# custom_keyboard.net
KiCad netlist of a schematic drawn in EAGLE
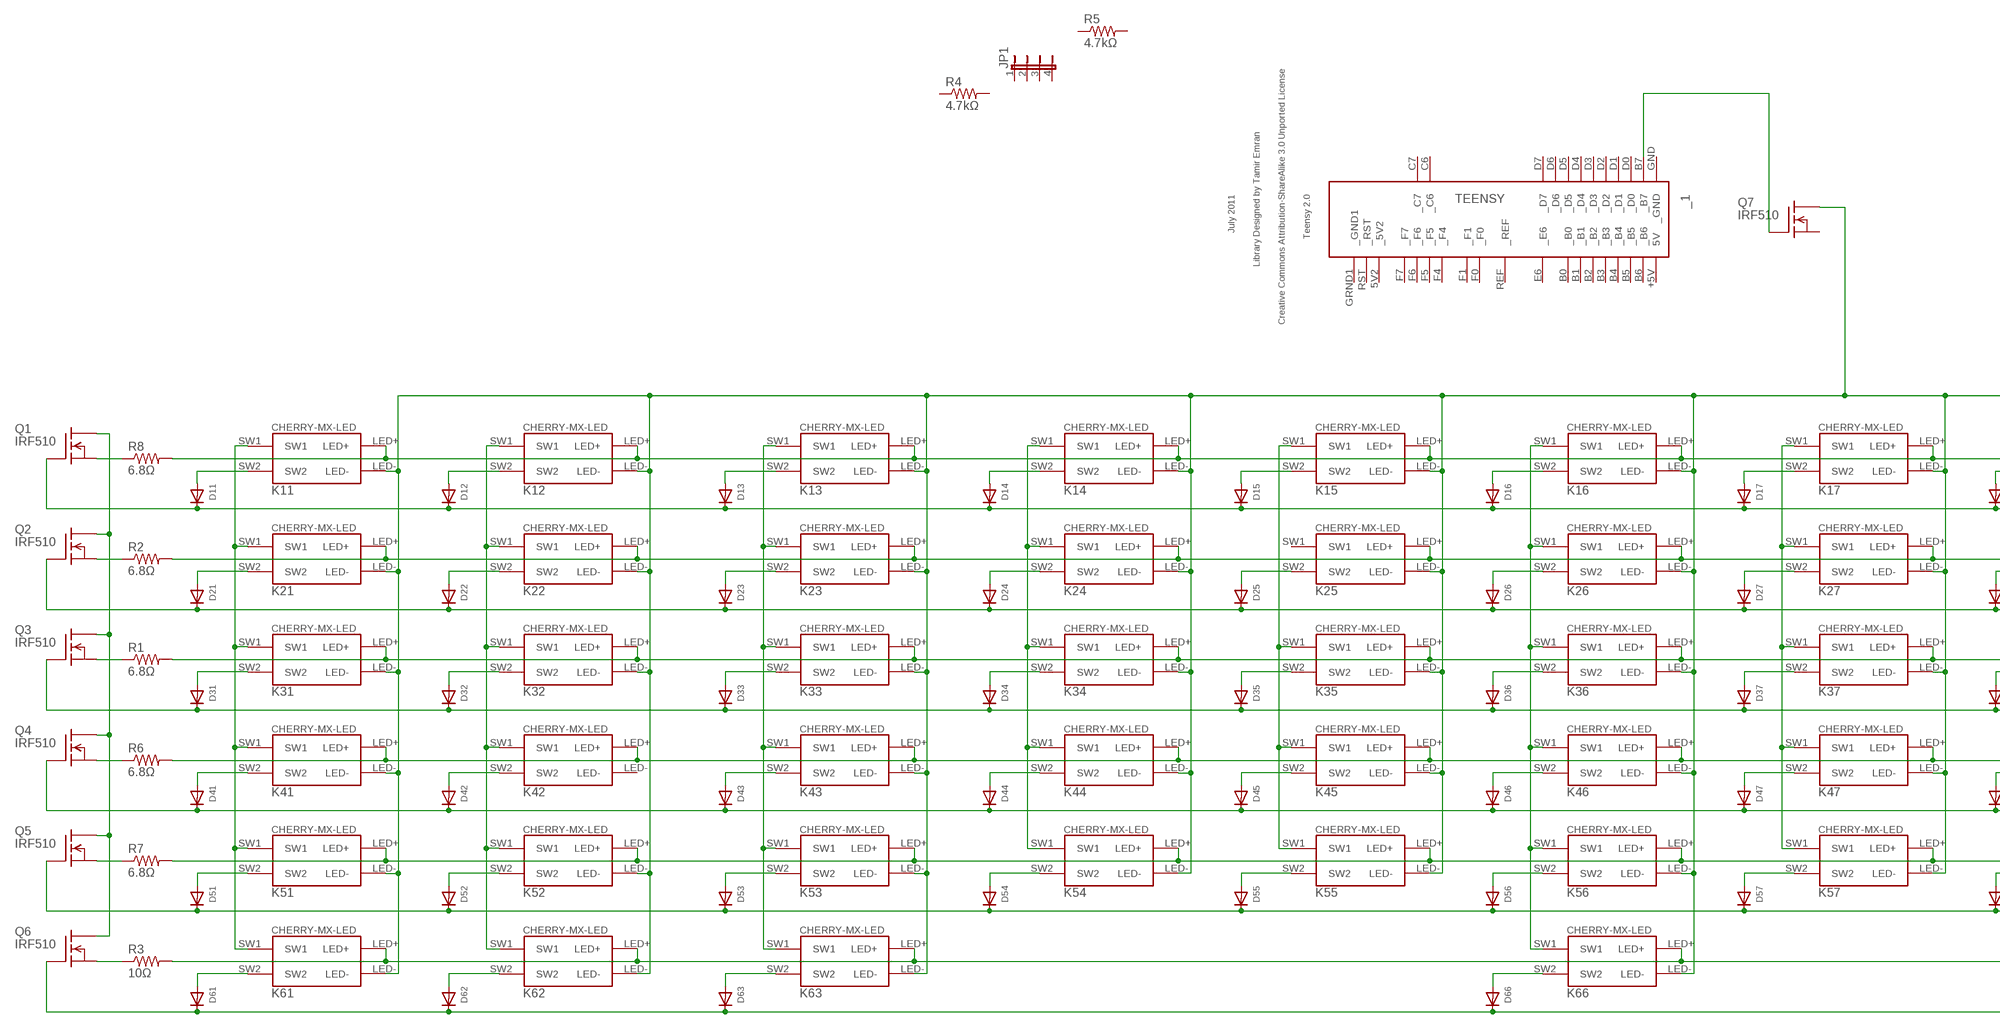
[diagram p0: schematic, sheet 1, part 1 of 2]
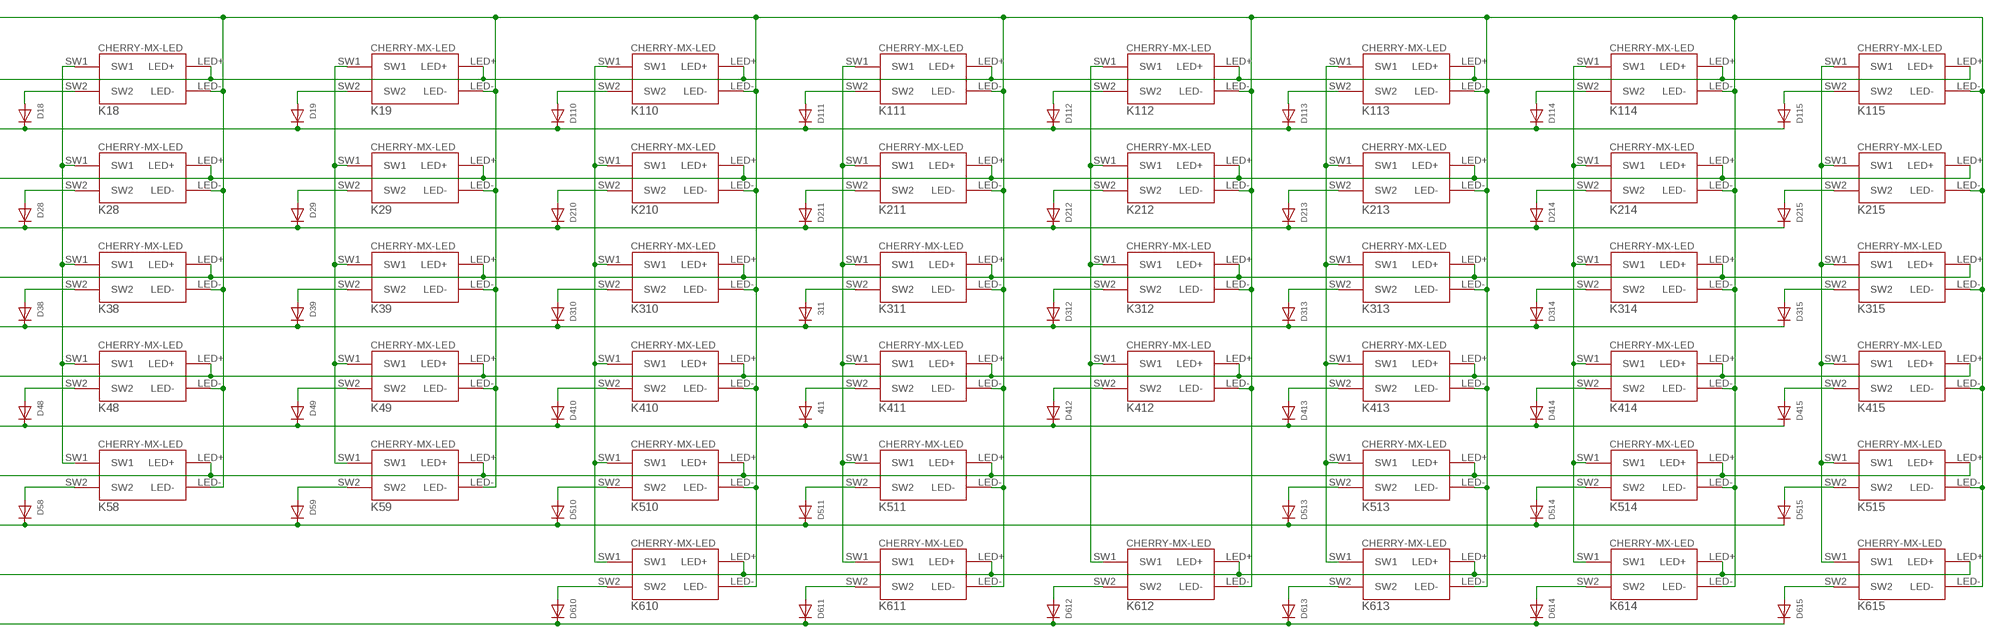
[diagram p1: schematic, sheet 1, part 2 of 2]

(export (version "E")
  (design (tool "Eeschema 10.0.6"))
  (components
    (comp (ref "311")
      (value "DIODEDO-1N4148")
      (footprint "eagle-import:DO-1N4148")
      (libsource (lib "eagle-import") (part "DIODEDO-1N4148"))
    )
    (comp (ref "411")
      (value "DIODEDO-1N4148")
      (footprint "eagle-import:DO-1N4148")
      (libsource (lib "eagle-import") (part "DIODEDO-1N4148"))
    )
    (comp (ref "D11")
      (value "DIODEDO-1N4148")
      (footprint "eagle-import:DO-1N4148")
      (libsource (lib "eagle-import") (part "DIODEDO-1N4148"))
    )
    (comp (ref "D12")
      (value "DIODEDO-1N4148")
      (footprint "eagle-import:DO-1N4148")
      (libsource (lib "eagle-import") (part "DIODEDO-1N4148"))
    )
    (comp (ref "D13")
      (value "DIODEDO-1N4148")
      (footprint "eagle-import:DO-1N4148")
      (libsource (lib "eagle-import") (part "DIODEDO-1N4148"))
    )
    (comp (ref "D14")
      (value "DIODEDO-1N4148")
      (footprint "eagle-import:DO-1N4148")
      (libsource (lib "eagle-import") (part "DIODEDO-1N4148"))
    )
    (comp (ref "D15")
      (value "DIODEDO-1N4148")
      (footprint "eagle-import:DO-1N4148")
      (libsource (lib "eagle-import") (part "DIODEDO-1N4148"))
    )
    (comp (ref "D16")
      (value "DIODEDO-1N4148")
      (footprint "eagle-import:DO-1N4148")
      (libsource (lib "eagle-import") (part "DIODEDO-1N4148"))
    )
    (comp (ref "D17")
      (value "DIODEDO-1N4148")
      (footprint "eagle-import:DO-1N4148")
      (libsource (lib "eagle-import") (part "DIODEDO-1N4148"))
    )
    (comp (ref "D18")
      (value "DIODEDO-1N4148")
      (footprint "eagle-import:DO-1N4148")
      (libsource (lib "eagle-import") (part "DIODEDO-1N4148"))
    )
    (comp (ref "D19")
      (value "DIODEDO-1N4148")
      (footprint "eagle-import:DO-1N4148")
      (libsource (lib "eagle-import") (part "DIODEDO-1N4148"))
    )
    (comp (ref "D21")
      (value "DIODEDO-1N4148")
      (footprint "eagle-import:DO-1N4148")
      (libsource (lib "eagle-import") (part "DIODEDO-1N4148"))
    )
    (comp (ref "D22")
      (value "DIODEDO-1N4148")
      (footprint "eagle-import:DO-1N4148")
      (libsource (lib "eagle-import") (part "DIODEDO-1N4148"))
    )
    (comp (ref "D23")
      (value "DIODEDO-1N4148")
      (footprint "eagle-import:DO-1N4148")
      (libsource (lib "eagle-import") (part "DIODEDO-1N4148"))
    )
    (comp (ref "D24")
      (value "DIODEDO-1N4148")
      (footprint "eagle-import:DO-1N4148")
      (libsource (lib "eagle-import") (part "DIODEDO-1N4148"))
    )
    (comp (ref "D25")
      (value "DIODEDO-1N4148")
      (footprint "eagle-import:DO-1N4148")
      (libsource (lib "eagle-import") (part "DIODEDO-1N4148"))
    )
    (comp (ref "D26")
      (value "DIODEDO-1N4148")
      (footprint "eagle-import:DO-1N4148")
      (libsource (lib "eagle-import") (part "DIODEDO-1N4148"))
    )
    (comp (ref "D27")
      (value "DIODEDO-1N4148")
      (footprint "eagle-import:DO-1N4148")
      (libsource (lib "eagle-import") (part "DIODEDO-1N4148"))
    )
    (comp (ref "D28")
      (value "DIODEDO-1N4148")
      (footprint "eagle-import:DO-1N4148")
      (libsource (lib "eagle-import") (part "DIODEDO-1N4148"))
    )
    (comp (ref "D29")
      (value "DIODEDO-1N4148")
      (footprint "eagle-import:DO-1N4148")
      (libsource (lib "eagle-import") (part "DIODEDO-1N4148"))
    )
    (comp (ref "D31")
      (value "DIODEDO-1N4148")
      (footprint "eagle-import:DO-1N4148")
      (libsource (lib "eagle-import") (part "DIODEDO-1N4148"))
    )
    (comp (ref "D32")
      (value "DIODEDO-1N4148")
      (footprint "eagle-import:DO-1N4148")
      (libsource (lib "eagle-import") (part "DIODEDO-1N4148"))
    )
    (comp (ref "D33")
      (value "DIODEDO-1N4148")
      (footprint "eagle-import:DO-1N4148")
      (libsource (lib "eagle-import") (part "DIODEDO-1N4148"))
    )
    (comp (ref "D34")
      (value "DIODEDO-1N4148")
      (footprint "eagle-import:DO-1N4148")
      (libsource (lib "eagle-import") (part "DIODEDO-1N4148"))
    )
    (comp (ref "D35")
      (value "DIODEDO-1N4148")
      (footprint "eagle-import:DO-1N4148")
      (libsource (lib "eagle-import") (part "DIODEDO-1N4148"))
    )
    (comp (ref "D36")
      (value "DIODEDO-1N4148")
      (footprint "eagle-import:DO-1N4148")
      (libsource (lib "eagle-import") (part "DIODEDO-1N4148"))
    )
    (comp (ref "D37")
      (value "DIODEDO-1N4148")
      (footprint "eagle-import:DO-1N4148")
      (libsource (lib "eagle-import") (part "DIODEDO-1N4148"))
    )
    (comp (ref "D38")
      (value "DIODEDO-1N4148")
      (footprint "eagle-import:DO-1N4148")
      (libsource (lib "eagle-import") (part "DIODEDO-1N4148"))
    )
    (comp (ref "D39")
      (value "DIODEDO-1N4148")
      (footprint "eagle-import:DO-1N4148")
      (libsource (lib "eagle-import") (part "DIODEDO-1N4148"))
    )
    (comp (ref "D41")
      (value "DIODEDO-1N4148")
      (footprint "eagle-import:DO-1N4148")
      (libsource (lib "eagle-import") (part "DIODEDO-1N4148"))
    )
    (comp (ref "D42")
      (value "DIODEDO-1N4148")
      (footprint "eagle-import:DO-1N4148")
      (libsource (lib "eagle-import") (part "DIODEDO-1N4148"))
    )
    (comp (ref "D43")
      (value "DIODEDO-1N4148")
      (footprint "eagle-import:DO-1N4148")
      (libsource (lib "eagle-import") (part "DIODEDO-1N4148"))
    )
    (comp (ref "D44")
      (value "DIODEDO-1N4148")
      (footprint "eagle-import:DO-1N4148")
      (libsource (lib "eagle-import") (part "DIODEDO-1N4148"))
    )
    (comp (ref "D45")
      (value "DIODEDO-1N4148")
      (footprint "eagle-import:DO-1N4148")
      (libsource (lib "eagle-import") (part "DIODEDO-1N4148"))
    )
    (comp (ref "D46")
      (value "DIODEDO-1N4148")
      (footprint "eagle-import:DO-1N4148")
      (libsource (lib "eagle-import") (part "DIODEDO-1N4148"))
    )
    (comp (ref "D47")
      (value "DIODEDO-1N4148")
      (footprint "eagle-import:DO-1N4148")
      (libsource (lib "eagle-import") (part "DIODEDO-1N4148"))
    )
    (comp (ref "D48")
      (value "DIODEDO-1N4148")
      (footprint "eagle-import:DO-1N4148")
      (libsource (lib "eagle-import") (part "DIODEDO-1N4148"))
    )
    (comp (ref "D49")
      (value "DIODEDO-1N4148")
      (footprint "eagle-import:DO-1N4148")
      (libsource (lib "eagle-import") (part "DIODEDO-1N4148"))
    )
    (comp (ref "D51")
      (value "DIODEDO-1N4148")
      (footprint "eagle-import:DO-1N4148")
      (libsource (lib "eagle-import") (part "DIODEDO-1N4148"))
    )
    (comp (ref "D52")
      (value "DIODEDO-1N4148")
      (footprint "eagle-import:DO-1N4148")
      (libsource (lib "eagle-import") (part "DIODEDO-1N4148"))
    )
    (comp (ref "D53")
      (value "DIODEDO-1N4148")
      (footprint "eagle-import:DO-1N4148")
      (libsource (lib "eagle-import") (part "DIODEDO-1N4148"))
    )
    (comp (ref "D54")
      (value "DIODEDO-1N4148")
      (footprint "eagle-import:DO-1N4148")
      (libsource (lib "eagle-import") (part "DIODEDO-1N4148"))
    )
    (comp (ref "D55")
      (value "DIODEDO-1N4148")
      (footprint "eagle-import:DO-1N4148")
      (libsource (lib "eagle-import") (part "DIODEDO-1N4148"))
    )
    (comp (ref "D56")
      (value "DIODEDO-1N4148")
      (footprint "eagle-import:DO-1N4148")
      (libsource (lib "eagle-import") (part "DIODEDO-1N4148"))
    )
    (comp (ref "D57")
      (value "DIODEDO-1N4148")
      (footprint "eagle-import:DO-1N4148")
      (libsource (lib "eagle-import") (part "DIODEDO-1N4148"))
    )
    (comp (ref "D58")
      (value "DIODEDO-1N4148")
      (footprint "eagle-import:DO-1N4148")
      (libsource (lib "eagle-import") (part "DIODEDO-1N4148"))
    )
    (comp (ref "D59")
      (value "DIODEDO-1N4148")
      (footprint "eagle-import:DO-1N4148")
      (libsource (lib "eagle-import") (part "DIODEDO-1N4148"))
    )
    (comp (ref "D61")
      (value "DIODEDO-1N4148")
      (footprint "eagle-import:DO-1N4148")
      (libsource (lib "eagle-import") (part "DIODEDO-1N4148"))
    )
    (comp (ref "D62")
      (value "DIODEDO-1N4148")
      (footprint "eagle-import:DO-1N4148")
      (libsource (lib "eagle-import") (part "DIODEDO-1N4148"))
    )
    (comp (ref "D63")
      (value "DIODEDO-1N4148")
      (footprint "eagle-import:DO-1N4148")
      (libsource (lib "eagle-import") (part "DIODEDO-1N4148"))
    )
    (comp (ref "D66")
      (value "DIODEDO-1N4148")
      (footprint "eagle-import:DO-1N4148")
      (libsource (lib "eagle-import") (part "DIODEDO-1N4148"))
    )
    (comp (ref "D110")
      (value "DIODEDO-1N4148")
      (footprint "eagle-import:DO-1N4148")
      (libsource (lib "eagle-import") (part "DIODEDO-1N4148"))
    )
    (comp (ref "D111")
      (value "DIODEDO-1N4148")
      (footprint "eagle-import:DO-1N4148")
      (libsource (lib "eagle-import") (part "DIODEDO-1N4148"))
    )
    (comp (ref "D112")
      (value "DIODEDO-1N4148")
      (footprint "eagle-import:DO-1N4148")
      (libsource (lib "eagle-import") (part "DIODEDO-1N4148"))
    )
    (comp (ref "D113")
      (value "DIODEDO-1N4148")
      (footprint "eagle-import:DO-1N4148")
      (libsource (lib "eagle-import") (part "DIODEDO-1N4148"))
    )
    (comp (ref "D114")
      (value "DIODEDO-1N4148")
      (footprint "eagle-import:DO-1N4148")
      (libsource (lib "eagle-import") (part "DIODEDO-1N4148"))
    )
    (comp (ref "D115")
      (value "DIODEDO-1N4148")
      (footprint "eagle-import:DO-1N4148")
      (libsource (lib "eagle-import") (part "DIODEDO-1N4148"))
    )
    (comp (ref "D210")
      (value "DIODEDO-1N4148")
      (footprint "eagle-import:DO-1N4148")
      (libsource (lib "eagle-import") (part "DIODEDO-1N4148"))
    )
    (comp (ref "D211")
      (value "DIODEDO-1N4148")
      (footprint "eagle-import:DO-1N4148")
      (libsource (lib "eagle-import") (part "DIODEDO-1N4148"))
    )
    (comp (ref "D212")
      (value "DIODEDO-1N4148")
      (footprint "eagle-import:DO-1N4148")
      (libsource (lib "eagle-import") (part "DIODEDO-1N4148"))
    )
    (comp (ref "D213")
      (value "DIODEDO-1N4148")
      (footprint "eagle-import:DO-1N4148")
      (libsource (lib "eagle-import") (part "DIODEDO-1N4148"))
    )
    (comp (ref "D214")
      (value "DIODEDO-1N4148")
      (footprint "eagle-import:DO-1N4148")
      (libsource (lib "eagle-import") (part "DIODEDO-1N4148"))
    )
    (comp (ref "D215")
      (value "DIODEDO-1N4148")
      (footprint "eagle-import:DO-1N4148")
      (libsource (lib "eagle-import") (part "DIODEDO-1N4148"))
    )
    (comp (ref "D310")
      (value "DIODEDO-1N4148")
      (footprint "eagle-import:DO-1N4148")
      (libsource (lib "eagle-import") (part "DIODEDO-1N4148"))
    )
    (comp (ref "D312")
      (value "DIODEDO-1N4148")
      (footprint "eagle-import:DO-1N4148")
      (libsource (lib "eagle-import") (part "DIODEDO-1N4148"))
    )
    (comp (ref "D313")
      (value "DIODEDO-1N4148")
      (footprint "eagle-import:DO-1N4148")
      (libsource (lib "eagle-import") (part "DIODEDO-1N4148"))
    )
    (comp (ref "D314")
      (value "DIODEDO-1N4148")
      (footprint "eagle-import:DO-1N4148")
      (libsource (lib "eagle-import") (part "DIODEDO-1N4148"))
    )
    (comp (ref "D315")
      (value "DIODEDO-1N4148")
      (footprint "eagle-import:DO-1N4148")
      (libsource (lib "eagle-import") (part "DIODEDO-1N4148"))
    )
    (comp (ref "D410")
      (value "DIODEDO-1N4148")
      (footprint "eagle-import:DO-1N4148")
      (libsource (lib "eagle-import") (part "DIODEDO-1N4148"))
    )
    (comp (ref "D412")
      (value "DIODEDO-1N4148")
      (footprint "eagle-import:DO-1N4148")
      (libsource (lib "eagle-import") (part "DIODEDO-1N4148"))
    )
    (comp (ref "D413")
      (value "DIODEDO-1N4148")
      (footprint "eagle-import:DO-1N4148")
      (libsource (lib "eagle-import") (part "DIODEDO-1N4148"))
    )
    (comp (ref "D414")
      (value "DIODEDO-1N4148")
      (footprint "eagle-import:DO-1N4148")
      (libsource (lib "eagle-import") (part "DIODEDO-1N4148"))
    )
    (comp (ref "D415")
      (value "DIODEDO-1N4148")
      (footprint "eagle-import:DO-1N4148")
      (libsource (lib "eagle-import") (part "DIODEDO-1N4148"))
    )
    (comp (ref "D510")
      (value "DIODEDO-1N4148")
      (footprint "eagle-import:DO-1N4148")
      (libsource (lib "eagle-import") (part "DIODEDO-1N4148"))
    )
    (comp (ref "D511")
      (value "DIODEDO-1N4148")
      (footprint "eagle-import:DO-1N4148")
      (libsource (lib "eagle-import") (part "DIODEDO-1N4148"))
    )
    (comp (ref "D513")
      (value "DIODEDO-1N4148")
      (footprint "eagle-import:DO-1N4148")
      (libsource (lib "eagle-import") (part "DIODEDO-1N4148"))
    )
    (comp (ref "D514")
      (value "DIODEDO-1N4148")
      (footprint "eagle-import:DO-1N4148")
      (libsource (lib "eagle-import") (part "DIODEDO-1N4148"))
    )
    (comp (ref "D515")
      (value "DIODEDO-1N4148")
      (footprint "eagle-import:DO-1N4148")
      (libsource (lib "eagle-import") (part "DIODEDO-1N4148"))
    )
    (comp (ref "D610")
      (value "DIODEDO-1N4148")
      (footprint "eagle-import:DO-1N4148")
      (libsource (lib "eagle-import") (part "DIODEDO-1N4148"))
    )
    (comp (ref "D611")
      (value "DIODEDO-1N4148")
      (footprint "eagle-import:DO-1N4148")
      (libsource (lib "eagle-import") (part "DIODEDO-1N4148"))
    )
    (comp (ref "D612")
      (value "DIODEDO-1N4148")
      (footprint "eagle-import:DO-1N4148")
      (libsource (lib "eagle-import") (part "DIODEDO-1N4148"))
    )
    (comp (ref "D613")
      (value "DIODEDO-1N4148")
      (footprint "eagle-import:DO-1N4148")
      (libsource (lib "eagle-import") (part "DIODEDO-1N4148"))
    )
    (comp (ref "D614")
      (value "DIODEDO-1N4148")
      (footprint "eagle-import:DO-1N4148")
      (libsource (lib "eagle-import") (part "DIODEDO-1N4148"))
    )
    (comp (ref "D615")
      (value "DIODEDO-1N4148")
      (footprint "eagle-import:DO-1N4148")
      (libsource (lib "eagle-import") (part "DIODEDO-1N4148"))
    )
    (comp (ref "JP1")
      (value "JP4E")
      (footprint "eagle-import:JP4")
      (libsource (lib "eagle-import") (part "JP4E"))
    )
    (comp (ref "K11")
      (value "CHERRY-MX-LED")
      (footprint "eagle-import:CHERRY-MX-LED")
      (libsource (lib "eagle-import") (part "CHERRY-MX-LED"))
    )
    (comp (ref "K12")
      (value "CHERRY-MX-LED")
      (footprint "eagle-import:CHERRY-MX-LED")
      (libsource (lib "eagle-import") (part "CHERRY-MX-LED"))
    )
    (comp (ref "K13")
      (value "CHERRY-MX-LED")
      (footprint "eagle-import:CHERRY-MX-LED")
      (libsource (lib "eagle-import") (part "CHERRY-MX-LED"))
    )
    (comp (ref "K14")
      (value "CHERRY-MX-LED")
      (footprint "eagle-import:CHERRY-MX-LED")
      (libsource (lib "eagle-import") (part "CHERRY-MX-LED"))
    )
    (comp (ref "K15")
      (value "CHERRY-MX-LED")
      (footprint "eagle-import:CHERRY-MX-LED")
      (libsource (lib "eagle-import") (part "CHERRY-MX-LED"))
    )
    (comp (ref "K16")
      (value "CHERRY-MX-LED")
      (footprint "eagle-import:CHERRY-MX-LED")
      (libsource (lib "eagle-import") (part "CHERRY-MX-LED"))
    )
    (comp (ref "K17")
      (value "CHERRY-MX-LED")
      (footprint "eagle-import:CHERRY-MX-LED")
      (libsource (lib "eagle-import") (part "CHERRY-MX-LED"))
    )
    (comp (ref "K18")
      (value "CHERRY-MX-LED")
      (footprint "eagle-import:CHERRY-MX-LED")
      (libsource (lib "eagle-import") (part "CHERRY-MX-LED"))
    )
    (comp (ref "K19")
      (value "CHERRY-MX-LED")
      (footprint "eagle-import:CHERRY-MX-LED")
      (libsource (lib "eagle-import") (part "CHERRY-MX-LED"))
    )
    (comp (ref "K21")
      (value "CHERRY-MX-LED")
      (footprint "eagle-import:CHERRY-MX-LED")
      (libsource (lib "eagle-import") (part "CHERRY-MX-LED"))
    )
    (comp (ref "K22")
      (value "CHERRY-MX-LED")
      (footprint "eagle-import:CHERRY-MX-LED")
      (libsource (lib "eagle-import") (part "CHERRY-MX-LED"))
    )
    (comp (ref "K23")
      (value "CHERRY-MX-LED")
      (footprint "eagle-import:CHERRY-MX-LED")
      (libsource (lib "eagle-import") (part "CHERRY-MX-LED"))
    )
    (comp (ref "K24")
      (value "CHERRY-MX-LED")
      (footprint "eagle-import:CHERRY-MX-LED")
      (libsource (lib "eagle-import") (part "CHERRY-MX-LED"))
    )
    (comp (ref "K25")
      (value "CHERRY-MX-LED")
      (footprint "eagle-import:CHERRY-MX-LED")
      (libsource (lib "eagle-import") (part "CHERRY-MX-LED"))
    )
    (comp (ref "K26")
      (value "CHERRY-MX-LED")
      (footprint "eagle-import:CHERRY-MX-LED")
      (libsource (lib "eagle-import") (part "CHERRY-MX-LED"))
    )
    (comp (ref "K27")
      (value "CHERRY-MX-LED")
      (footprint "eagle-import:CHERRY-MX-LED")
      (libsource (lib "eagle-import") (part "CHERRY-MX-LED"))
    )
    (comp (ref "K28")
      (value "CHERRY-MX-LED")
      (footprint "eagle-import:CHERRY-MX-LED")
      (libsource (lib "eagle-import") (part "CHERRY-MX-LED"))
    )
    (comp (ref "K29")
      (value "CHERRY-MX-LED")
      (footprint "eagle-import:CHERRY-MX-LED")
      (libsource (lib "eagle-import") (part "CHERRY-MX-LED"))
    )
    (comp (ref "K31")
      (value "CHERRY-MX-LED")
      (footprint "eagle-import:CHERRY-MX-LED")
      (libsource (lib "eagle-import") (part "CHERRY-MX-LED"))
    )
    (comp (ref "K32")
      (value "CHERRY-MX-LED")
      (footprint "eagle-import:CHERRY-MX-LED")
      (libsource (lib "eagle-import") (part "CHERRY-MX-LED"))
    )
    (comp (ref "K33")
      (value "CHERRY-MX-LED")
      (footprint "eagle-import:CHERRY-MX-LED")
      (libsource (lib "eagle-import") (part "CHERRY-MX-LED"))
    )
    (comp (ref "K34")
      (value "CHERRY-MX-LED")
      (footprint "eagle-import:CHERRY-MX-LED")
      (libsource (lib "eagle-import") (part "CHERRY-MX-LED"))
    )
    (comp (ref "K35")
      (value "CHERRY-MX-LED")
      (footprint "eagle-import:CHERRY-MX-LED")
      (libsource (lib "eagle-import") (part "CHERRY-MX-LED"))
    )
    (comp (ref "K36")
      (value "CHERRY-MX-LED")
      (footprint "eagle-import:CHERRY-MX-LED")
      (libsource (lib "eagle-import") (part "CHERRY-MX-LED"))
    )
    (comp (ref "K37")
      (value "CHERRY-MX-LED")
      (footprint "eagle-import:CHERRY-MX-LED")
      (libsource (lib "eagle-import") (part "CHERRY-MX-LED"))
    )
    (comp (ref "K38")
      (value "CHERRY-MX-LED")
      (footprint "eagle-import:CHERRY-MX-LED")
      (libsource (lib "eagle-import") (part "CHERRY-MX-LED"))
    )
    (comp (ref "K39")
      (value "CHERRY-MX-LED")
      (footprint "eagle-import:CHERRY-MX-LED")
      (libsource (lib "eagle-import") (part "CHERRY-MX-LED"))
    )
    (comp (ref "K41")
      (value "CHERRY-MX-LED")
      (footprint "eagle-import:CHERRY-MX-LED")
      (libsource (lib "eagle-import") (part "CHERRY-MX-LED"))
    )
    (comp (ref "K42")
      (value "CHERRY-MX-LED")
      (footprint "eagle-import:CHERRY-MX-LED")
      (libsource (lib "eagle-import") (part "CHERRY-MX-LED"))
    )
    (comp (ref "K43")
      (value "CHERRY-MX-LED")
      (footprint "eagle-import:CHERRY-MX-LED")
      (libsource (lib "eagle-import") (part "CHERRY-MX-LED"))
    )
    (comp (ref "K44")
      (value "CHERRY-MX-LED")
      (footprint "eagle-import:CHERRY-MX-LED")
      (libsource (lib "eagle-import") (part "CHERRY-MX-LED"))
    )
    (comp (ref "K45")
      (value "CHERRY-MX-LED")
      (footprint "eagle-import:CHERRY-MX-LED")
      (libsource (lib "eagle-import") (part "CHERRY-MX-LED"))
    )
    (comp (ref "K46")
      (value "CHERRY-MX-LED")
      (footprint "eagle-import:CHERRY-MX-LED")
      (libsource (lib "eagle-import") (part "CHERRY-MX-LED"))
    )
    (comp (ref "K47")
      (value "CHERRY-MX-LED")
      (footprint "eagle-import:CHERRY-MX-LED")
      (libsource (lib "eagle-import") (part "CHERRY-MX-LED"))
    )
    (comp (ref "K48")
      (value "CHERRY-MX-LED")
      (footprint "eagle-import:CHERRY-MX-LED")
      (libsource (lib "eagle-import") (part "CHERRY-MX-LED"))
    )
    (comp (ref "K49")
      (value "CHERRY-MX-LED")
      (footprint "eagle-import:CHERRY-MX-LED")
      (libsource (lib "eagle-import") (part "CHERRY-MX-LED"))
    )
    (comp (ref "K51")
      (value "CHERRY-MX-LED")
      (footprint "eagle-import:CHERRY-MX-LED")
      (libsource (lib "eagle-import") (part "CHERRY-MX-LED"))
    )
    (comp (ref "K52")
      (value "CHERRY-MX-LED")
      (footprint "eagle-import:CHERRY-MX-LED")
      (libsource (lib "eagle-import") (part "CHERRY-MX-LED"))
    )
    (comp (ref "K53")
      (value "CHERRY-MX-LED")
      (footprint "eagle-import:CHERRY-MX-LED")
      (libsource (lib "eagle-import") (part "CHERRY-MX-LED"))
    )
    (comp (ref "K54")
      (value "CHERRY-MX-LED")
      (footprint "eagle-import:CHERRY-MX-LED")
      (libsource (lib "eagle-import") (part "CHERRY-MX-LED"))
    )
    (comp (ref "K55")
      (value "CHERRY-MX-LED")
      (footprint "eagle-import:CHERRY-MX-LED")
      (libsource (lib "eagle-import") (part "CHERRY-MX-LED"))
    )
    (comp (ref "K56")
      (value "CHERRY-MX-LED")
      (footprint "eagle-import:CHERRY-MX-LED")
      (libsource (lib "eagle-import") (part "CHERRY-MX-LED"))
    )
    (comp (ref "K57")
      (value "CHERRY-MX-LED")
      (footprint "eagle-import:CHERRY-MX-LED")
      (libsource (lib "eagle-import") (part "CHERRY-MX-LED"))
    )
    (comp (ref "K58")
      (value "CHERRY-MX-LED")
      (footprint "eagle-import:CHERRY-MX-LED")
      (libsource (lib "eagle-import") (part "CHERRY-MX-LED"))
    )
    (comp (ref "K59")
      (value "CHERRY-MX-LED")
      (footprint "eagle-import:CHERRY-MX-LED")
      (libsource (lib "eagle-import") (part "CHERRY-MX-LED"))
    )
    (comp (ref "K61")
      (value "CHERRY-MX-LED")
      (footprint "eagle-import:CHERRY-MX-LED")
      (libsource (lib "eagle-import") (part "CHERRY-MX-LED"))
    )
    (comp (ref "K62")
      (value "CHERRY-MX-LED")
      (footprint "eagle-import:CHERRY-MX-LED")
      (libsource (lib "eagle-import") (part "CHERRY-MX-LED"))
    )
    (comp (ref "K63")
      (value "CHERRY-MX-LED")
      (footprint "eagle-import:CHERRY-MX-LED")
      (libsource (lib "eagle-import") (part "CHERRY-MX-LED"))
    )
    (comp (ref "K66")
      (value "CHERRY-MX-LED")
      (footprint "eagle-import:CHERRY-MX-LED")
      (libsource (lib "eagle-import") (part "CHERRY-MX-LED"))
    )
    (comp (ref "K110")
      (value "CHERRY-MX-LED")
      (footprint "eagle-import:CHERRY-MX-LED")
      (libsource (lib "eagle-import") (part "CHERRY-MX-LED"))
    )
    (comp (ref "K111")
      (value "CHERRY-MX-LED")
      (footprint "eagle-import:CHERRY-MX-LED")
      (libsource (lib "eagle-import") (part "CHERRY-MX-LED"))
    )
    (comp (ref "K112")
      (value "CHERRY-MX-LED")
      (footprint "eagle-import:CHERRY-MX-LED")
      (libsource (lib "eagle-import") (part "CHERRY-MX-LED"))
    )
    (comp (ref "K113")
      (value "CHERRY-MX-LED")
      (footprint "eagle-import:CHERRY-MX-LED")
      (libsource (lib "eagle-import") (part "CHERRY-MX-LED"))
    )
    (comp (ref "K114")
      (value "CHERRY-MX-LED")
      (footprint "eagle-import:CHERRY-MX-LED")
      (libsource (lib "eagle-import") (part "CHERRY-MX-LED"))
    )
    (comp (ref "K115")
      (value "CHERRY-MX-LED")
      (footprint "eagle-import:CHERRY-MX-LED")
      (libsource (lib "eagle-import") (part "CHERRY-MX-LED"))
    )
    (comp (ref "K210")
      (value "CHERRY-MX-LED")
      (footprint "eagle-import:CHERRY-MX-LED")
      (libsource (lib "eagle-import") (part "CHERRY-MX-LED"))
    )
    (comp (ref "K211")
      (value "CHERRY-MX-LED")
      (footprint "eagle-import:CHERRY-MX-LED")
      (libsource (lib "eagle-import") (part "CHERRY-MX-LED"))
    )
    (comp (ref "K212")
      (value "CHERRY-MX-LED")
      (footprint "eagle-import:CHERRY-MX-LED")
      (libsource (lib "eagle-import") (part "CHERRY-MX-LED"))
    )
    (comp (ref "K213")
      (value "CHERRY-MX-LED")
      (footprint "eagle-import:CHERRY-MX-LED")
      (libsource (lib "eagle-import") (part "CHERRY-MX-LED"))
    )
    (comp (ref "K214")
      (value "CHERRY-MX-LED")
      (footprint "eagle-import:CHERRY-MX-LED")
      (libsource (lib "eagle-import") (part "CHERRY-MX-LED"))
    )
    (comp (ref "K215")
      (value "CHERRY-MX-LED")
      (footprint "eagle-import:CHERRY-MX-LED")
      (libsource (lib "eagle-import") (part "CHERRY-MX-LED"))
    )
    (comp (ref "K310")
      (value "CHERRY-MX-LED")
      (footprint "eagle-import:CHERRY-MX-LED")
      (libsource (lib "eagle-import") (part "CHERRY-MX-LED"))
    )
    (comp (ref "K311")
      (value "CHERRY-MX-LED")
      (footprint "eagle-import:CHERRY-MX-LED")
      (libsource (lib "eagle-import") (part "CHERRY-MX-LED"))
    )
    (comp (ref "K312")
      (value "CHERRY-MX-LED")
      (footprint "eagle-import:CHERRY-MX-LED")
      (libsource (lib "eagle-import") (part "CHERRY-MX-LED"))
    )
    (comp (ref "K313")
      (value "CHERRY-MX-LED")
      (footprint "eagle-import:CHERRY-MX-LED")
      (libsource (lib "eagle-import") (part "CHERRY-MX-LED"))
    )
    (comp (ref "K314")
      (value "CHERRY-MX-LED")
      (footprint "eagle-import:CHERRY-MX-LED")
      (libsource (lib "eagle-import") (part "CHERRY-MX-LED"))
    )
    (comp (ref "K315")
      (value "CHERRY-MX-LED")
      (footprint "eagle-import:CHERRY-MX-LED")
      (libsource (lib "eagle-import") (part "CHERRY-MX-LED"))
    )
    (comp (ref "K410")
      (value "CHERRY-MX-LED")
      (footprint "eagle-import:CHERRY-MX-LED")
      (libsource (lib "eagle-import") (part "CHERRY-MX-LED"))
    )
    (comp (ref "K411")
      (value "CHERRY-MX-LED")
      (footprint "eagle-import:CHERRY-MX-LED")
      (libsource (lib "eagle-import") (part "CHERRY-MX-LED"))
    )
    (comp (ref "K412")
      (value "CHERRY-MX-LED")
      (footprint "eagle-import:CHERRY-MX-LED")
      (libsource (lib "eagle-import") (part "CHERRY-MX-LED"))
    )
    (comp (ref "K413")
      (value "CHERRY-MX-LED")
      (footprint "eagle-import:CHERRY-MX-LED")
      (libsource (lib "eagle-import") (part "CHERRY-MX-LED"))
    )
    (comp (ref "K414")
      (value "CHERRY-MX-LED")
      (footprint "eagle-import:CHERRY-MX-LED")
      (libsource (lib "eagle-import") (part "CHERRY-MX-LED"))
    )
    (comp (ref "K415")
      (value "CHERRY-MX-LED")
      (footprint "eagle-import:CHERRY-MX-LED")
      (libsource (lib "eagle-import") (part "CHERRY-MX-LED"))
    )
    (comp (ref "K510")
      (value "CHERRY-MX-LED")
      (footprint "eagle-import:CHERRY-MX-LED")
      (libsource (lib "eagle-import") (part "CHERRY-MX-LED"))
    )
    (comp (ref "K511")
      (value "CHERRY-MX-LED")
      (footprint "eagle-import:CHERRY-MX-LED")
      (libsource (lib "eagle-import") (part "CHERRY-MX-LED"))
    )
    (comp (ref "K513")
      (value "CHERRY-MX-LED")
      (footprint "eagle-import:CHERRY-MX-LED")
      (libsource (lib "eagle-import") (part "CHERRY-MX-LED"))
    )
    (comp (ref "K514")
      (value "CHERRY-MX-LED")
      (footprint "eagle-import:CHERRY-MX-LED")
      (libsource (lib "eagle-import") (part "CHERRY-MX-LED"))
    )
    (comp (ref "K515")
      (value "CHERRY-MX-LED")
      (footprint "eagle-import:CHERRY-MX-LED")
      (libsource (lib "eagle-import") (part "CHERRY-MX-LED"))
    )
    (comp (ref "K610")
      (value "CHERRY-MX-LED")
      (footprint "eagle-import:CHERRY-MX-LED")
      (libsource (lib "eagle-import") (part "CHERRY-MX-LED"))
    )
    (comp (ref "K611")
      (value "CHERRY-MX-LED")
      (footprint "eagle-import:CHERRY-MX-LED")
      (libsource (lib "eagle-import") (part "CHERRY-MX-LED"))
    )
    (comp (ref "K612")
      (value "CHERRY-MX-LED")
      (footprint "eagle-import:CHERRY-MX-LED")
      (libsource (lib "eagle-import") (part "CHERRY-MX-LED"))
    )
    (comp (ref "K613")
      (value "CHERRY-MX-LED")
      (footprint "eagle-import:CHERRY-MX-LED")
      (libsource (lib "eagle-import") (part "CHERRY-MX-LED"))
    )
    (comp (ref "K614")
      (value "CHERRY-MX-LED")
      (footprint "eagle-import:CHERRY-MX-LED")
      (libsource (lib "eagle-import") (part "CHERRY-MX-LED"))
    )
    (comp (ref "K615")
      (value "CHERRY-MX-LED")
      (footprint "eagle-import:CHERRY-MX-LED")
      (libsource (lib "eagle-import") (part "CHERRY-MX-LED"))
    )
    (comp (ref "Q1")
      (value "IRF510")
      (footprint "eagle-import:TO220")
      (libsource (lib "eagle-import") (part "IRF510"))
    )
    (comp (ref "Q2")
      (value "IRF510")
      (footprint "eagle-import:TO220")
      (libsource (lib "eagle-import") (part "IRF510"))
    )
    (comp (ref "Q3")
      (value "IRF510")
      (footprint "eagle-import:TO220")
      (libsource (lib "eagle-import") (part "IRF510"))
    )
    (comp (ref "Q4")
      (value "IRF510")
      (footprint "eagle-import:TO220")
      (libsource (lib "eagle-import") (part "IRF510"))
    )
    (comp (ref "Q5")
      (value "IRF510")
      (footprint "eagle-import:TO220")
      (libsource (lib "eagle-import") (part "IRF510"))
    )
    (comp (ref "Q6")
      (value "IRF510")
      (footprint "eagle-import:TO220")
      (libsource (lib "eagle-import") (part "IRF510"))
    )
    (comp (ref "Q7")
      (value "IRF510")
      (footprint "eagle-import:TO220")
      (libsource (lib "eagle-import") (part "IRF510"))
    )
    (comp (ref "R1")
      (value "6.8Ω")
      (footprint "eagle-import:0411_12")
      (libsource (lib "eagle-import") (part "R-US_0411/12"))
    )
    (comp (ref "R2")
      (value "6.8Ω")
      (footprint "eagle-import:0411_12")
      (libsource (lib "eagle-import") (part "R-US_0411/12"))
    )
    (comp (ref "R3")
      (value "10Ω")
      (footprint "eagle-import:0411_12")
      (libsource (lib "eagle-import") (part "R-US_0411/12"))
    )
    (comp (ref "R4")
      (value "4.7kΩ")
      (footprint "eagle-import:0204_7")
      (libsource (lib "eagle-import") (part "R-US_0204/7"))
    )
    (comp (ref "R5")
      (value "4.7kΩ")
      (footprint "eagle-import:0204_7")
      (libsource (lib "eagle-import") (part "R-US_0204/7"))
    )
    (comp (ref "R6")
      (value "6.8Ω")
      (footprint "eagle-import:0411_12")
      (libsource (lib "eagle-import") (part "R-US_0411/12"))
    )
    (comp (ref "R7")
      (value "6.8Ω")
      (footprint "eagle-import:0411_12")
      (libsource (lib "eagle-import") (part "R-US_0411/12"))
    )
    (comp (ref "R8")
      (value "6.8Ω")
      (footprint "eagle-import:0411_12")
      (libsource (lib "eagle-import") (part "R-US_0411/12"))
    )
    (comp (ref "_1")
      (value "TEENSY")
      (footprint "eagle-import:TEENSY")
      (libsource (lib "eagle-import") (part "TEENSY"))
    )
  )
  (nets
    (net (code "1") (name "Net-(311-PadA)") (class "Default")
      (node (ref "311") (pin "A") (pinfunction "A_A") (pintype "passive"))
      (node (ref "K311") (pin "SW2") (pinfunction "SW2_SW2") (pintype "bidirectional"))
    )
    (net (code "2") (name "Net-(411-PadA)") (class "Default")
      (node (ref "411") (pin "A") (pinfunction "A_A") (pintype "passive"))
      (node (ref "K411") (pin "SW2") (pinfunction "SW2_SW2") (pintype "bidirectional"))
    )
    (net (code "3") (name "Net-(D11-PadA)") (class "Default")
      (node (ref "D11") (pin "A") (pinfunction "A_A") (pintype "passive"))
      (node (ref "K11") (pin "SW2") (pinfunction "SW2_SW2") (pintype "bidirectional"))
    )
    (net (code "4") (name "Net-(D12-PadA)") (class "Default")
      (node (ref "D12") (pin "A") (pinfunction "A_A") (pintype "passive"))
      (node (ref "K12") (pin "SW2") (pinfunction "SW2_SW2") (pintype "bidirectional"))
    )
    (net (code "5") (name "Net-(D13-PadA)") (class "Default")
      (node (ref "D13") (pin "A") (pinfunction "A_A") (pintype "passive"))
      (node (ref "K13") (pin "SW2") (pinfunction "SW2_SW2") (pintype "bidirectional"))
    )
    (net (code "6") (name "Net-(D14-PadA)") (class "Default")
      (node (ref "D14") (pin "A") (pinfunction "A_A") (pintype "passive"))
      (node (ref "K14") (pin "SW2") (pinfunction "SW2_SW2") (pintype "bidirectional"))
    )
    (net (code "7") (name "Net-(D15-PadA)") (class "Default")
      (node (ref "D15") (pin "A") (pinfunction "A_A") (pintype "passive"))
      (node (ref "K15") (pin "SW2") (pinfunction "SW2_SW2") (pintype "bidirectional"))
    )
    (net (code "8") (name "Net-(D16-PadA)") (class "Default")
      (node (ref "D16") (pin "A") (pinfunction "A_A") (pintype "passive"))
      (node (ref "K16") (pin "SW2") (pinfunction "SW2_SW2") (pintype "bidirectional"))
    )
    (net (code "9") (name "Net-(D17-PadA)") (class "Default")
      (node (ref "D17") (pin "A") (pinfunction "A_A") (pintype "passive"))
      (node (ref "K17") (pin "SW2") (pinfunction "SW2_SW2") (pintype "bidirectional"))
    )
    (net (code "10") (name "Net-(D18-PadA)") (class "Default")
      (node (ref "D18") (pin "A") (pinfunction "A_A") (pintype "passive"))
      (node (ref "K18") (pin "SW2") (pinfunction "SW2_SW2") (pintype "bidirectional"))
    )
    (net (code "11") (name "Net-(D19-PadA)") (class "Default")
      (node (ref "D19") (pin "A") (pinfunction "A_A") (pintype "passive"))
      (node (ref "K19") (pin "SW2") (pinfunction "SW2_SW2") (pintype "bidirectional"))
    )
    (net (code "12") (name "Net-(D21-PadA)") (class "Default")
      (node (ref "D21") (pin "A") (pinfunction "A_A") (pintype "passive"))
      (node (ref "K21") (pin "SW2") (pinfunction "SW2_SW2") (pintype "bidirectional"))
    )
    (net (code "13") (name "Net-(D22-PadA)") (class "Default")
      (node (ref "D22") (pin "A") (pinfunction "A_A") (pintype "passive"))
      (node (ref "K22") (pin "SW2") (pinfunction "SW2_SW2") (pintype "bidirectional"))
    )
    (net (code "14") (name "Net-(D23-PadA)") (class "Default")
      (node (ref "D23") (pin "A") (pinfunction "A_A") (pintype "passive"))
      (node (ref "K23") (pin "SW2") (pinfunction "SW2_SW2") (pintype "bidirectional"))
    )
    (net (code "15") (name "Net-(D24-PadA)") (class "Default")
      (node (ref "D24") (pin "A") (pinfunction "A_A") (pintype "passive"))
      (node (ref "K24") (pin "SW2") (pinfunction "SW2_SW2") (pintype "bidirectional"))
    )
    (net (code "16") (name "Net-(D25-PadA)") (class "Default")
      (node (ref "D25") (pin "A") (pinfunction "A_A") (pintype "passive"))
      (node (ref "K25") (pin "SW2") (pinfunction "SW2_SW2") (pintype "bidirectional"))
    )
    (net (code "17") (name "Net-(D26-PadA)") (class "Default")
      (node (ref "D26") (pin "A") (pinfunction "A_A") (pintype "passive"))
      (node (ref "K26") (pin "SW2") (pinfunction "SW2_SW2") (pintype "bidirectional"))
    )
    (net (code "18") (name "Net-(D27-PadA)") (class "Default")
      (node (ref "D27") (pin "A") (pinfunction "A_A") (pintype "passive"))
      (node (ref "K27") (pin "SW2") (pinfunction "SW2_SW2") (pintype "bidirectional"))
    )
    (net (code "19") (name "Net-(D28-PadA)") (class "Default")
      (node (ref "D28") (pin "A") (pinfunction "A_A") (pintype "passive"))
      (node (ref "K28") (pin "SW2") (pinfunction "SW2_SW2") (pintype "bidirectional"))
    )
    (net (code "20") (name "Net-(D29-PadA)") (class "Default")
      (node (ref "D29") (pin "A") (pinfunction "A_A") (pintype "passive"))
      (node (ref "K29") (pin "SW2") (pinfunction "SW2_SW2") (pintype "bidirectional"))
    )
    (net (code "21") (name "Net-(D31-PadA)") (class "Default")
      (node (ref "D31") (pin "A") (pinfunction "A_A") (pintype "passive"))
      (node (ref "K31") (pin "SW2") (pinfunction "SW2_SW2") (pintype "bidirectional"))
    )
    (net (code "22") (name "Net-(D32-PadA)") (class "Default")
      (node (ref "D32") (pin "A") (pinfunction "A_A") (pintype "passive"))
      (node (ref "K32") (pin "SW2") (pinfunction "SW2_SW2") (pintype "bidirectional"))
    )
    (net (code "23") (name "Net-(D33-PadA)") (class "Default")
      (node (ref "D33") (pin "A") (pinfunction "A_A") (pintype "passive"))
      (node (ref "K33") (pin "SW2") (pinfunction "SW2_SW2") (pintype "bidirectional"))
    )
    (net (code "24") (name "Net-(D34-PadA)") (class "Default")
      (node (ref "D34") (pin "A") (pinfunction "A_A") (pintype "passive"))
      (node (ref "K34") (pin "SW2") (pinfunction "SW2_SW2") (pintype "bidirectional"))
    )
    (net (code "25") (name "Net-(D35-PadA)") (class "Default")
      (node (ref "D35") (pin "A") (pinfunction "A_A") (pintype "passive"))
      (node (ref "K35") (pin "SW2") (pinfunction "SW2_SW2") (pintype "bidirectional"))
    )
    (net (code "26") (name "Net-(D36-PadA)") (class "Default")
      (node (ref "D36") (pin "A") (pinfunction "A_A") (pintype "passive"))
      (node (ref "K36") (pin "SW2") (pinfunction "SW2_SW2") (pintype "bidirectional"))
    )
    (net (code "27") (name "Net-(D37-PadA)") (class "Default")
      (node (ref "D37") (pin "A") (pinfunction "A_A") (pintype "passive"))
      (node (ref "K37") (pin "SW2") (pinfunction "SW2_SW2") (pintype "bidirectional"))
    )
    (net (code "28") (name "Net-(D38-PadA)") (class "Default")
      (node (ref "D38") (pin "A") (pinfunction "A_A") (pintype "passive"))
      (node (ref "K38") (pin "SW2") (pinfunction "SW2_SW2") (pintype "bidirectional"))
    )
    (net (code "29") (name "Net-(D39-PadA)") (class "Default")
      (node (ref "D39") (pin "A") (pinfunction "A_A") (pintype "passive"))
      (node (ref "K39") (pin "SW2") (pinfunction "SW2_SW2") (pintype "bidirectional"))
    )
    (net (code "30") (name "Net-(D41-PadA)") (class "Default")
      (node (ref "D41") (pin "A") (pinfunction "A_A") (pintype "passive"))
      (node (ref "K41") (pin "SW2") (pinfunction "SW2_SW2") (pintype "bidirectional"))
    )
    (net (code "31") (name "Net-(D42-PadA)") (class "Default")
      (node (ref "D42") (pin "A") (pinfunction "A_A") (pintype "passive"))
      (node (ref "K42") (pin "SW2") (pinfunction "SW2_SW2") (pintype "bidirectional"))
    )
    (net (code "32") (name "Net-(D43-PadA)") (class "Default")
      (node (ref "D43") (pin "A") (pinfunction "A_A") (pintype "passive"))
      (node (ref "K43") (pin "SW2") (pinfunction "SW2_SW2") (pintype "bidirectional"))
    )
    (net (code "33") (name "Net-(D44-PadA)") (class "Default")
      (node (ref "D44") (pin "A") (pinfunction "A_A") (pintype "passive"))
      (node (ref "K44") (pin "SW2") (pinfunction "SW2_SW2") (pintype "bidirectional"))
    )
    (net (code "34") (name "Net-(D45-PadA)") (class "Default")
      (node (ref "D45") (pin "A") (pinfunction "A_A") (pintype "passive"))
      (node (ref "K45") (pin "SW2") (pinfunction "SW2_SW2") (pintype "bidirectional"))
    )
    (net (code "35") (name "Net-(D46-PadA)") (class "Default")
      (node (ref "D46") (pin "A") (pinfunction "A_A") (pintype "passive"))
      (node (ref "K46") (pin "SW2") (pinfunction "SW2_SW2") (pintype "bidirectional"))
    )
    (net (code "36") (name "Net-(D47-PadA)") (class "Default")
      (node (ref "D47") (pin "A") (pinfunction "A_A") (pintype "passive"))
      (node (ref "K47") (pin "SW2") (pinfunction "SW2_SW2") (pintype "bidirectional"))
    )
    (net (code "37") (name "Net-(D48-PadA)") (class "Default")
      (node (ref "D48") (pin "A") (pinfunction "A_A") (pintype "passive"))
      (node (ref "K48") (pin "SW2") (pinfunction "SW2_SW2") (pintype "bidirectional"))
    )
    (net (code "38") (name "Net-(D49-PadA)") (class "Default")
      (node (ref "D49") (pin "A") (pinfunction "A_A") (pintype "passive"))
      (node (ref "K49") (pin "SW2") (pinfunction "SW2_SW2") (pintype "bidirectional"))
    )
    (net (code "39") (name "Net-(D51-PadA)") (class "Default")
      (node (ref "D51") (pin "A") (pinfunction "A_A") (pintype "passive"))
      (node (ref "K51") (pin "SW2") (pinfunction "SW2_SW2") (pintype "bidirectional"))
    )
    (net (code "40") (name "Net-(D52-PadA)") (class "Default")
      (node (ref "D52") (pin "A") (pinfunction "A_A") (pintype "passive"))
      (node (ref "K52") (pin "SW2") (pinfunction "SW2_SW2") (pintype "bidirectional"))
    )
    (net (code "41") (name "Net-(D53-PadA)") (class "Default")
      (node (ref "D53") (pin "A") (pinfunction "A_A") (pintype "passive"))
      (node (ref "K53") (pin "SW2") (pinfunction "SW2_SW2") (pintype "bidirectional"))
    )
    (net (code "42") (name "Net-(D54-PadA)") (class "Default")
      (node (ref "D54") (pin "A") (pinfunction "A_A") (pintype "passive"))
      (node (ref "K54") (pin "SW2") (pinfunction "SW2_SW2") (pintype "bidirectional"))
    )
    (net (code "43") (name "Net-(D55-PadA)") (class "Default")
      (node (ref "D55") (pin "A") (pinfunction "A_A") (pintype "passive"))
      (node (ref "K55") (pin "SW2") (pinfunction "SW2_SW2") (pintype "bidirectional"))
    )
    (net (code "44") (name "Net-(D56-PadA)") (class "Default")
      (node (ref "D56") (pin "A") (pinfunction "A_A") (pintype "passive"))
      (node (ref "K56") (pin "SW2") (pinfunction "SW2_SW2") (pintype "bidirectional"))
    )
    (net (code "45") (name "Net-(D57-PadA)") (class "Default")
      (node (ref "D57") (pin "A") (pinfunction "A_A") (pintype "passive"))
      (node (ref "K57") (pin "SW2") (pinfunction "SW2_SW2") (pintype "bidirectional"))
    )
    (net (code "46") (name "Net-(D58-PadA)") (class "Default")
      (node (ref "D58") (pin "A") (pinfunction "A_A") (pintype "passive"))
      (node (ref "K58") (pin "SW2") (pinfunction "SW2_SW2") (pintype "bidirectional"))
    )
    (net (code "47") (name "Net-(D59-PadA)") (class "Default")
      (node (ref "D59") (pin "A") (pinfunction "A_A") (pintype "passive"))
      (node (ref "K59") (pin "SW2") (pinfunction "SW2_SW2") (pintype "bidirectional"))
    )
    (net (code "48") (name "Net-(D61-PadA)") (class "Default")
      (node (ref "D61") (pin "A") (pinfunction "A_A") (pintype "passive"))
      (node (ref "K61") (pin "SW2") (pinfunction "SW2_SW2") (pintype "bidirectional"))
    )
    (net (code "49") (name "Net-(D62-PadA)") (class "Default")
      (node (ref "D62") (pin "A") (pinfunction "A_A") (pintype "passive"))
      (node (ref "K62") (pin "SW2") (pinfunction "SW2_SW2") (pintype "bidirectional"))
    )
    (net (code "50") (name "Net-(D63-PadA)") (class "Default")
      (node (ref "D63") (pin "A") (pinfunction "A_A") (pintype "passive"))
      (node (ref "K63") (pin "SW2") (pinfunction "SW2_SW2") (pintype "bidirectional"))
    )
    (net (code "51") (name "Net-(D66-PadA)") (class "Default")
      (node (ref "D66") (pin "A") (pinfunction "A_A") (pintype "passive"))
      (node (ref "K66") (pin "SW2") (pinfunction "SW2_SW2") (pintype "bidirectional"))
    )
    (net (code "52") (name "Net-(D110-PadA)") (class "Default")
      (node (ref "D110") (pin "A") (pinfunction "A_A") (pintype "passive"))
      (node (ref "K110") (pin "SW2") (pinfunction "SW2_SW2") (pintype "bidirectional"))
    )
    (net (code "53") (name "Net-(D111-PadA)") (class "Default")
      (node (ref "D111") (pin "A") (pinfunction "A_A") (pintype "passive"))
      (node (ref "K111") (pin "SW2") (pinfunction "SW2_SW2") (pintype "bidirectional"))
    )
    (net (code "54") (name "Net-(D112-PadA)") (class "Default")
      (node (ref "D112") (pin "A") (pinfunction "A_A") (pintype "passive"))
      (node (ref "K112") (pin "SW2") (pinfunction "SW2_SW2") (pintype "bidirectional"))
    )
    (net (code "55") (name "Net-(D113-PadA)") (class "Default")
      (node (ref "D113") (pin "A") (pinfunction "A_A") (pintype "passive"))
      (node (ref "K113") (pin "SW2") (pinfunction "SW2_SW2") (pintype "bidirectional"))
    )
    (net (code "56") (name "Net-(D114-PadA)") (class "Default")
      (node (ref "D114") (pin "A") (pinfunction "A_A") (pintype "passive"))
      (node (ref "K114") (pin "SW2") (pinfunction "SW2_SW2") (pintype "bidirectional"))
    )
    (net (code "57") (name "Net-(D115-PadA)") (class "Default")
      (node (ref "D115") (pin "A") (pinfunction "A_A") (pintype "passive"))
      (node (ref "K115") (pin "SW2") (pinfunction "SW2_SW2") (pintype "bidirectional"))
    )
    (net (code "58") (name "Net-(D210-PadA)") (class "Default")
      (node (ref "D210") (pin "A") (pinfunction "A_A") (pintype "passive"))
      (node (ref "K210") (pin "SW2") (pinfunction "SW2_SW2") (pintype "bidirectional"))
    )
    (net (code "59") (name "Net-(D211-PadA)") (class "Default")
      (node (ref "D211") (pin "A") (pinfunction "A_A") (pintype "passive"))
      (node (ref "K211") (pin "SW2") (pinfunction "SW2_SW2") (pintype "bidirectional"))
    )
    (net (code "60") (name "Net-(D212-PadA)") (class "Default")
      (node (ref "D212") (pin "A") (pinfunction "A_A") (pintype "passive"))
      (node (ref "K212") (pin "SW2") (pinfunction "SW2_SW2") (pintype "bidirectional"))
    )
    (net (code "61") (name "Net-(D213-PadA)") (class "Default")
      (node (ref "D213") (pin "A") (pinfunction "A_A") (pintype "passive"))
      (node (ref "K213") (pin "SW2") (pinfunction "SW2_SW2") (pintype "bidirectional"))
    )
    (net (code "62") (name "Net-(D214-PadA)") (class "Default")
      (node (ref "D214") (pin "A") (pinfunction "A_A") (pintype "passive"))
      (node (ref "K214") (pin "SW2") (pinfunction "SW2_SW2") (pintype "bidirectional"))
    )
    (net (code "63") (name "Net-(D215-PadA)") (class "Default")
      (node (ref "D215") (pin "A") (pinfunction "A_A") (pintype "passive"))
      (node (ref "K215") (pin "SW2") (pinfunction "SW2_SW2") (pintype "bidirectional"))
    )
    (net (code "64") (name "Net-(D310-PadA)") (class "Default")
      (node (ref "D310") (pin "A") (pinfunction "A_A") (pintype "passive"))
      (node (ref "K310") (pin "SW2") (pinfunction "SW2_SW2") (pintype "bidirectional"))
    )
    (net (code "65") (name "Net-(D312-PadA)") (class "Default")
      (node (ref "D312") (pin "A") (pinfunction "A_A") (pintype "passive"))
      (node (ref "K312") (pin "SW2") (pinfunction "SW2_SW2") (pintype "bidirectional"))
    )
    (net (code "66") (name "Net-(D313-PadA)") (class "Default")
      (node (ref "D313") (pin "A") (pinfunction "A_A") (pintype "passive"))
      (node (ref "K313") (pin "SW2") (pinfunction "SW2_SW2") (pintype "bidirectional"))
    )
    (net (code "67") (name "Net-(D314-PadA)") (class "Default")
      (node (ref "D314") (pin "A") (pinfunction "A_A") (pintype "passive"))
      (node (ref "K314") (pin "SW2") (pinfunction "SW2_SW2") (pintype "bidirectional"))
    )
    (net (code "68") (name "Net-(D315-PadA)") (class "Default")
      (node (ref "D315") (pin "A") (pinfunction "A_A") (pintype "passive"))
      (node (ref "K315") (pin "SW2") (pinfunction "SW2_SW2") (pintype "bidirectional"))
    )
    (net (code "69") (name "Net-(D410-PadA)") (class "Default")
      (node (ref "D410") (pin "A") (pinfunction "A_A") (pintype "passive"))
      (node (ref "K410") (pin "SW2") (pinfunction "SW2_SW2") (pintype "bidirectional"))
    )
    (net (code "70") (name "Net-(D412-PadA)") (class "Default")
      (node (ref "D412") (pin "A") (pinfunction "A_A") (pintype "passive"))
      (node (ref "K412") (pin "SW2") (pinfunction "SW2_SW2") (pintype "bidirectional"))
    )
    (net (code "71") (name "Net-(D413-PadA)") (class "Default")
      (node (ref "D413") (pin "A") (pinfunction "A_A") (pintype "passive"))
      (node (ref "K413") (pin "SW2") (pinfunction "SW2_SW2") (pintype "bidirectional"))
    )
    (net (code "72") (name "Net-(D414-PadA)") (class "Default")
      (node (ref "D414") (pin "A") (pinfunction "A_A") (pintype "passive"))
      (node (ref "K414") (pin "SW2") (pinfunction "SW2_SW2") (pintype "bidirectional"))
    )
    (net (code "73") (name "Net-(D415-PadA)") (class "Default")
      (node (ref "D415") (pin "A") (pinfunction "A_A") (pintype "passive"))
      (node (ref "K415") (pin "SW2") (pinfunction "SW2_SW2") (pintype "bidirectional"))
    )
    (net (code "74") (name "Net-(D510-PadA)") (class "Default")
      (node (ref "D510") (pin "A") (pinfunction "A_A") (pintype "passive"))
      (node (ref "K510") (pin "SW2") (pinfunction "SW2_SW2") (pintype "bidirectional"))
    )
    (net (code "75") (name "Net-(D511-PadA)") (class "Default")
      (node (ref "D511") (pin "A") (pinfunction "A_A") (pintype "passive"))
      (node (ref "K511") (pin "SW2") (pinfunction "SW2_SW2") (pintype "bidirectional"))
    )
    (net (code "76") (name "Net-(D513-PadA)") (class "Default")
      (node (ref "D513") (pin "A") (pinfunction "A_A") (pintype "passive"))
      (node (ref "K513") (pin "SW2") (pinfunction "SW2_SW2") (pintype "bidirectional"))
    )
    (net (code "77") (name "Net-(D514-PadA)") (class "Default")
      (node (ref "D514") (pin "A") (pinfunction "A_A") (pintype "passive"))
      (node (ref "K514") (pin "SW2") (pinfunction "SW2_SW2") (pintype "bidirectional"))
    )
    (net (code "78") (name "Net-(D515-PadA)") (class "Default")
      (node (ref "D515") (pin "A") (pinfunction "A_A") (pintype "passive"))
      (node (ref "K515") (pin "SW2") (pinfunction "SW2_SW2") (pintype "bidirectional"))
    )
    (net (code "79") (name "Net-(D610-PadA)") (class "Default")
      (node (ref "D610") (pin "A") (pinfunction "A_A") (pintype "passive"))
      (node (ref "K610") (pin "SW2") (pinfunction "SW2_SW2") (pintype "bidirectional"))
    )
    (net (code "80") (name "Net-(D611-PadA)") (class "Default")
      (node (ref "D611") (pin "A") (pinfunction "A_A") (pintype "passive"))
      (node (ref "K611") (pin "SW2") (pinfunction "SW2_SW2") (pintype "bidirectional"))
    )
    (net (code "81") (name "Net-(D612-PadA)") (class "Default")
      (node (ref "D612") (pin "A") (pinfunction "A_A") (pintype "passive"))
      (node (ref "K612") (pin "SW2") (pinfunction "SW2_SW2") (pintype "bidirectional"))
    )
    (net (code "82") (name "Net-(D613-PadA)") (class "Default")
      (node (ref "D613") (pin "A") (pinfunction "A_A") (pintype "passive"))
      (node (ref "K613") (pin "SW2") (pinfunction "SW2_SW2") (pintype "bidirectional"))
    )
    (net (code "83") (name "Net-(D614-PadA)") (class "Default")
      (node (ref "D614") (pin "A") (pinfunction "A_A") (pintype "passive"))
      (node (ref "K614") (pin "SW2") (pinfunction "SW2_SW2") (pintype "bidirectional"))
    )
    (net (code "84") (name "Net-(D615-PadA)") (class "Default")
      (node (ref "D615") (pin "A") (pinfunction "A_A") (pintype "passive"))
      (node (ref "K615") (pin "SW2") (pinfunction "SW2_SW2") (pintype "bidirectional"))
    )
    (net (code "85") (name "Net-(K11-PadLED+)") (class "Default")
      (node (ref "K11") (pin "LED+") (pinfunction "LED+_LED+") (pintype "bidirectional"))
      (node (ref "K110") (pin "LED+") (pinfunction "LED+_LED+") (pintype "bidirectional"))
      (node (ref "K111") (pin "LED+") (pinfunction "LED+_LED+") (pintype "bidirectional"))
      (node (ref "K112") (pin "LED+") (pinfunction "LED+_LED+") (pintype "bidirectional"))
      (node (ref "K113") (pin "LED+") (pinfunction "LED+_LED+") (pintype "bidirectional"))
      (node (ref "K114") (pin "LED+") (pinfunction "LED+_LED+") (pintype "bidirectional"))
      (node (ref "K115") (pin "LED+") (pinfunction "LED+_LED+") (pintype "bidirectional"))
      (node (ref "K12") (pin "LED+") (pinfunction "LED+_LED+") (pintype "bidirectional"))
      (node (ref "K13") (pin "LED+") (pinfunction "LED+_LED+") (pintype "bidirectional"))
      (node (ref "K14") (pin "LED+") (pinfunction "LED+_LED+") (pintype "bidirectional"))
      (node (ref "K15") (pin "LED+") (pinfunction "LED+_LED+") (pintype "bidirectional"))
      (node (ref "K16") (pin "LED+") (pinfunction "LED+_LED+") (pintype "bidirectional"))
      (node (ref "K17") (pin "LED+") (pinfunction "LED+_LED+") (pintype "bidirectional"))
      (node (ref "K18") (pin "LED+") (pinfunction "LED+_LED+") (pintype "bidirectional"))
      (node (ref "K19") (pin "LED+") (pinfunction "LED+_LED+") (pintype "bidirectional"))
      (node (ref "R8") (pin "2") (pinfunction "2_2") (pintype "passive"))
    )
    (net (code "86") (name "Net-(K11-PadSW1)") (class "Default")
      (node (ref "K11") (pin "SW1") (pinfunction "SW1_SW1") (pintype "bidirectional"))
      (node (ref "K21") (pin "SW1") (pinfunction "SW1_SW1") (pintype "bidirectional"))
      (node (ref "K31") (pin "SW1") (pinfunction "SW1_SW1") (pintype "bidirectional"))
      (node (ref "K41") (pin "SW1") (pinfunction "SW1_SW1") (pintype "bidirectional"))
      (node (ref "K51") (pin "SW1") (pinfunction "SW1_SW1") (pintype "bidirectional"))
      (node (ref "K61") (pin "SW1") (pinfunction "SW1_SW1") (pintype "bidirectional"))
    )
    (net (code "87") (name "Net-(K12-PadSW1)") (class "Default")
      (node (ref "K12") (pin "SW1") (pinfunction "SW1_SW1") (pintype "bidirectional"))
      (node (ref "K22") (pin "SW1") (pinfunction "SW1_SW1") (pintype "bidirectional"))
      (node (ref "K32") (pin "SW1") (pinfunction "SW1_SW1") (pintype "bidirectional"))
      (node (ref "K42") (pin "SW1") (pinfunction "SW1_SW1") (pintype "bidirectional"))
      (node (ref "K52") (pin "SW1") (pinfunction "SW1_SW1") (pintype "bidirectional"))
      (node (ref "K62") (pin "SW1") (pinfunction "SW1_SW1") (pintype "bidirectional"))
    )
    (net (code "88") (name "Net-(K13-PadSW1)") (class "Default")
      (node (ref "K13") (pin "SW1") (pinfunction "SW1_SW1") (pintype "bidirectional"))
      (node (ref "K23") (pin "SW1") (pinfunction "SW1_SW1") (pintype "bidirectional"))
      (node (ref "K33") (pin "SW1") (pinfunction "SW1_SW1") (pintype "bidirectional"))
      (node (ref "K43") (pin "SW1") (pinfunction "SW1_SW1") (pintype "bidirectional"))
      (node (ref "K53") (pin "SW1") (pinfunction "SW1_SW1") (pintype "bidirectional"))
      (node (ref "K63") (pin "SW1") (pinfunction "SW1_SW1") (pintype "bidirectional"))
    )
    (net (code "89") (name "Net-(K14-PadSW1)") (class "Default")
      (node (ref "K14") (pin "SW1") (pinfunction "SW1_SW1") (pintype "bidirectional"))
      (node (ref "K24") (pin "SW1") (pinfunction "SW1_SW1") (pintype "bidirectional"))
      (node (ref "K34") (pin "SW1") (pinfunction "SW1_SW1") (pintype "bidirectional"))
      (node (ref "K44") (pin "SW1") (pinfunction "SW1_SW1") (pintype "bidirectional"))
      (node (ref "K54") (pin "SW1") (pinfunction "SW1_SW1") (pintype "bidirectional"))
    )
    (net (code "90") (name "Net-(K15-PadSW1)") (class "Default")
      (node (ref "K15") (pin "SW1") (pinfunction "SW1_SW1") (pintype "bidirectional"))
      (node (ref "K35") (pin "SW1") (pinfunction "SW1_SW1") (pintype "bidirectional"))
      (node (ref "K45") (pin "SW1") (pinfunction "SW1_SW1") (pintype "bidirectional"))
      (node (ref "K55") (pin "SW1") (pinfunction "SW1_SW1") (pintype "bidirectional"))
    )
    (net (code "91") (name "Net-(K16-PadSW1)") (class "Default")
      (node (ref "K16") (pin "SW1") (pinfunction "SW1_SW1") (pintype "bidirectional"))
      (node (ref "K26") (pin "SW1") (pinfunction "SW1_SW1") (pintype "bidirectional"))
      (node (ref "K36") (pin "SW1") (pinfunction "SW1_SW1") (pintype "bidirectional"))
      (node (ref "K46") (pin "SW1") (pinfunction "SW1_SW1") (pintype "bidirectional"))
      (node (ref "K56") (pin "SW1") (pinfunction "SW1_SW1") (pintype "bidirectional"))
      (node (ref "K66") (pin "SW1") (pinfunction "SW1_SW1") (pintype "bidirectional"))
    )
    (net (code "92") (name "Net-(K17-PadSW1)") (class "Default")
      (node (ref "K17") (pin "SW1") (pinfunction "SW1_SW1") (pintype "bidirectional"))
      (node (ref "K27") (pin "SW1") (pinfunction "SW1_SW1") (pintype "bidirectional"))
      (node (ref "K37") (pin "SW1") (pinfunction "SW1_SW1") (pintype "bidirectional"))
      (node (ref "K47") (pin "SW1") (pinfunction "SW1_SW1") (pintype "bidirectional"))
      (node (ref "K57") (pin "SW1") (pinfunction "SW1_SW1") (pintype "bidirectional"))
    )
    (net (code "93") (name "Net-(K18-PadSW1)") (class "Default")
      (node (ref "K18") (pin "SW1") (pinfunction "SW1_SW1") (pintype "bidirectional"))
      (node (ref "K28") (pin "SW1") (pinfunction "SW1_SW1") (pintype "bidirectional"))
      (node (ref "K38") (pin "SW1") (pinfunction "SW1_SW1") (pintype "bidirectional"))
      (node (ref "K48") (pin "SW1") (pinfunction "SW1_SW1") (pintype "bidirectional"))
      (node (ref "K58") (pin "SW1") (pinfunction "SW1_SW1") (pintype "bidirectional"))
    )
    (net (code "94") (name "Net-(K19-PadSW1)") (class "Default")
      (node (ref "K19") (pin "SW1") (pinfunction "SW1_SW1") (pintype "bidirectional"))
      (node (ref "K29") (pin "SW1") (pinfunction "SW1_SW1") (pintype "bidirectional"))
      (node (ref "K39") (pin "SW1") (pinfunction "SW1_SW1") (pintype "bidirectional"))
      (node (ref "K49") (pin "SW1") (pinfunction "SW1_SW1") (pintype "bidirectional"))
      (node (ref "K59") (pin "SW1") (pinfunction "SW1_SW1") (pintype "bidirectional"))
    )
    (net (code "95") (name "Net-(K21-PadLED+)") (class "Default")
      (node (ref "K21") (pin "LED+") (pinfunction "LED+_LED+") (pintype "bidirectional"))
      (node (ref "K210") (pin "LED+") (pinfunction "LED+_LED+") (pintype "bidirectional"))
      (node (ref "K211") (pin "LED+") (pinfunction "LED+_LED+") (pintype "bidirectional"))
      (node (ref "K212") (pin "LED+") (pinfunction "LED+_LED+") (pintype "bidirectional"))
      (node (ref "K213") (pin "LED+") (pinfunction "LED+_LED+") (pintype "bidirectional"))
      (node (ref "K214") (pin "LED+") (pinfunction "LED+_LED+") (pintype "bidirectional"))
      (node (ref "K215") (pin "LED+") (pinfunction "LED+_LED+") (pintype "bidirectional"))
      (node (ref "K22") (pin "LED+") (pinfunction "LED+_LED+") (pintype "bidirectional"))
      (node (ref "K23") (pin "LED+") (pinfunction "LED+_LED+") (pintype "bidirectional"))
      (node (ref "K24") (pin "LED+") (pinfunction "LED+_LED+") (pintype "bidirectional"))
      (node (ref "K25") (pin "LED+") (pinfunction "LED+_LED+") (pintype "bidirectional"))
      (node (ref "K26") (pin "LED+") (pinfunction "LED+_LED+") (pintype "bidirectional"))
      (node (ref "K27") (pin "LED+") (pinfunction "LED+_LED+") (pintype "bidirectional"))
      (node (ref "K28") (pin "LED+") (pinfunction "LED+_LED+") (pintype "bidirectional"))
      (node (ref "K29") (pin "LED+") (pinfunction "LED+_LED+") (pintype "bidirectional"))
      (node (ref "R2") (pin "2") (pinfunction "2_2") (pintype "passive"))
    )
    (net (code "96") (name "Net-(K31-PadLED+)") (class "Default")
      (node (ref "K31") (pin "LED+") (pinfunction "LED+_LED+") (pintype "bidirectional"))
      (node (ref "K310") (pin "LED+") (pinfunction "LED+_LED+") (pintype "bidirectional"))
      (node (ref "K311") (pin "LED+") (pinfunction "LED+_LED+") (pintype "bidirectional"))
      (node (ref "K312") (pin "LED+") (pinfunction "LED+_LED+") (pintype "bidirectional"))
      (node (ref "K313") (pin "LED+") (pinfunction "LED+_LED+") (pintype "bidirectional"))
      (node (ref "K314") (pin "LED+") (pinfunction "LED+_LED+") (pintype "bidirectional"))
      (node (ref "K315") (pin "LED+") (pinfunction "LED+_LED+") (pintype "bidirectional"))
      (node (ref "K32") (pin "LED+") (pinfunction "LED+_LED+") (pintype "bidirectional"))
      (node (ref "K33") (pin "LED+") (pinfunction "LED+_LED+") (pintype "bidirectional"))
      (node (ref "K34") (pin "LED+") (pinfunction "LED+_LED+") (pintype "bidirectional"))
      (node (ref "K35") (pin "LED+") (pinfunction "LED+_LED+") (pintype "bidirectional"))
      (node (ref "K36") (pin "LED+") (pinfunction "LED+_LED+") (pintype "bidirectional"))
      (node (ref "K37") (pin "LED+") (pinfunction "LED+_LED+") (pintype "bidirectional"))
      (node (ref "K38") (pin "LED+") (pinfunction "LED+_LED+") (pintype "bidirectional"))
      (node (ref "K39") (pin "LED+") (pinfunction "LED+_LED+") (pintype "bidirectional"))
      (node (ref "R1") (pin "2") (pinfunction "2_2") (pintype "passive"))
    )
    (net (code "97") (name "Net-(K41-PadLED+)") (class "Default")
      (node (ref "K41") (pin "LED+") (pinfunction "LED+_LED+") (pintype "bidirectional"))
      (node (ref "K410") (pin "LED+") (pinfunction "LED+_LED+") (pintype "bidirectional"))
      (node (ref "K411") (pin "LED+") (pinfunction "LED+_LED+") (pintype "bidirectional"))
      (node (ref "K412") (pin "LED+") (pinfunction "LED+_LED+") (pintype "bidirectional"))
      (node (ref "K413") (pin "LED+") (pinfunction "LED+_LED+") (pintype "bidirectional"))
      (node (ref "K414") (pin "LED+") (pinfunction "LED+_LED+") (pintype "bidirectional"))
      (node (ref "K415") (pin "LED+") (pinfunction "LED+_LED+") (pintype "bidirectional"))
      (node (ref "K42") (pin "LED+") (pinfunction "LED+_LED+") (pintype "bidirectional"))
      (node (ref "K43") (pin "LED+") (pinfunction "LED+_LED+") (pintype "bidirectional"))
      (node (ref "K44") (pin "LED+") (pinfunction "LED+_LED+") (pintype "bidirectional"))
      (node (ref "K45") (pin "LED+") (pinfunction "LED+_LED+") (pintype "bidirectional"))
      (node (ref "K46") (pin "LED+") (pinfunction "LED+_LED+") (pintype "bidirectional"))
      (node (ref "K47") (pin "LED+") (pinfunction "LED+_LED+") (pintype "bidirectional"))
      (node (ref "K48") (pin "LED+") (pinfunction "LED+_LED+") (pintype "bidirectional"))
      (node (ref "K49") (pin "LED+") (pinfunction "LED+_LED+") (pintype "bidirectional"))
      (node (ref "R6") (pin "2") (pinfunction "2_2") (pintype "passive"))
    )
    (net (code "98") (name "Net-(K51-PadLED+)") (class "Default")
      (node (ref "K51") (pin "LED+") (pinfunction "LED+_LED+") (pintype "bidirectional"))
      (node (ref "K510") (pin "LED+") (pinfunction "LED+_LED+") (pintype "bidirectional"))
      (node (ref "K511") (pin "LED+") (pinfunction "LED+_LED+") (pintype "bidirectional"))
      (node (ref "K513") (pin "LED+") (pinfunction "LED+_LED+") (pintype "bidirectional"))
      (node (ref "K514") (pin "LED+") (pinfunction "LED+_LED+") (pintype "bidirectional"))
      (node (ref "K515") (pin "LED+") (pinfunction "LED+_LED+") (pintype "bidirectional"))
      (node (ref "K52") (pin "LED+") (pinfunction "LED+_LED+") (pintype "bidirectional"))
      (node (ref "K53") (pin "LED+") (pinfunction "LED+_LED+") (pintype "bidirectional"))
      (node (ref "K54") (pin "LED+") (pinfunction "LED+_LED+") (pintype "bidirectional"))
      (node (ref "K55") (pin "LED+") (pinfunction "LED+_LED+") (pintype "bidirectional"))
      (node (ref "K56") (pin "LED+") (pinfunction "LED+_LED+") (pintype "bidirectional"))
      (node (ref "K57") (pin "LED+") (pinfunction "LED+_LED+") (pintype "bidirectional"))
      (node (ref "K58") (pin "LED+") (pinfunction "LED+_LED+") (pintype "bidirectional"))
      (node (ref "K59") (pin "LED+") (pinfunction "LED+_LED+") (pintype "bidirectional"))
      (node (ref "R7") (pin "2") (pinfunction "2_2") (pintype "passive"))
    )
    (net (code "99") (name "Net-(K61-PadLED+)") (class "Default")
      (node (ref "K61") (pin "LED+") (pinfunction "LED+_LED+") (pintype "bidirectional"))
      (node (ref "K610") (pin "LED+") (pinfunction "LED+_LED+") (pintype "bidirectional"))
      (node (ref "K611") (pin "LED+") (pinfunction "LED+_LED+") (pintype "bidirectional"))
      (node (ref "K612") (pin "LED+") (pinfunction "LED+_LED+") (pintype "bidirectional"))
      (node (ref "K613") (pin "LED+") (pinfunction "LED+_LED+") (pintype "bidirectional"))
      (node (ref "K614") (pin "LED+") (pinfunction "LED+_LED+") (pintype "bidirectional"))
      (node (ref "K615") (pin "LED+") (pinfunction "LED+_LED+") (pintype "bidirectional"))
      (node (ref "K62") (pin "LED+") (pinfunction "LED+_LED+") (pintype "bidirectional"))
      (node (ref "K63") (pin "LED+") (pinfunction "LED+_LED+") (pintype "bidirectional"))
      (node (ref "K66") (pin "LED+") (pinfunction "LED+_LED+") (pintype "bidirectional"))
      (node (ref "R3") (pin "2") (pinfunction "2_2") (pintype "passive"))
    )
    (net (code "100") (name "Net-(K110-PadSW1)") (class "Default")
      (node (ref "K110") (pin "SW1") (pinfunction "SW1_SW1") (pintype "bidirectional"))
      (node (ref "K210") (pin "SW1") (pinfunction "SW1_SW1") (pintype "bidirectional"))
      (node (ref "K310") (pin "SW1") (pinfunction "SW1_SW1") (pintype "bidirectional"))
      (node (ref "K410") (pin "SW1") (pinfunction "SW1_SW1") (pintype "bidirectional"))
      (node (ref "K510") (pin "SW1") (pinfunction "SW1_SW1") (pintype "bidirectional"))
      (node (ref "K610") (pin "SW1") (pinfunction "SW1_SW1") (pintype "bidirectional"))
    )
    (net (code "101") (name "Net-(K111-PadSW1)") (class "Default")
      (node (ref "K111") (pin "SW1") (pinfunction "SW1_SW1") (pintype "bidirectional"))
      (node (ref "K211") (pin "SW1") (pinfunction "SW1_SW1") (pintype "bidirectional"))
      (node (ref "K311") (pin "SW1") (pinfunction "SW1_SW1") (pintype "bidirectional"))
      (node (ref "K411") (pin "SW1") (pinfunction "SW1_SW1") (pintype "bidirectional"))
      (node (ref "K511") (pin "SW1") (pinfunction "SW1_SW1") (pintype "bidirectional"))
      (node (ref "K611") (pin "SW1") (pinfunction "SW1_SW1") (pintype "bidirectional"))
    )
    (net (code "102") (name "Net-(K112-PadSW1)") (class "Default")
      (node (ref "K112") (pin "SW1") (pinfunction "SW1_SW1") (pintype "bidirectional"))
      (node (ref "K212") (pin "SW1") (pinfunction "SW1_SW1") (pintype "bidirectional"))
      (node (ref "K312") (pin "SW1") (pinfunction "SW1_SW1") (pintype "bidirectional"))
      (node (ref "K412") (pin "SW1") (pinfunction "SW1_SW1") (pintype "bidirectional"))
      (node (ref "K612") (pin "SW1") (pinfunction "SW1_SW1") (pintype "bidirectional"))
    )
    (net (code "103") (name "Net-(K113-PadSW1)") (class "Default")
      (node (ref "K113") (pin "SW1") (pinfunction "SW1_SW1") (pintype "bidirectional"))
      (node (ref "K213") (pin "SW1") (pinfunction "SW1_SW1") (pintype "bidirectional"))
      (node (ref "K313") (pin "SW1") (pinfunction "SW1_SW1") (pintype "bidirectional"))
      (node (ref "K413") (pin "SW1") (pinfunction "SW1_SW1") (pintype "bidirectional"))
      (node (ref "K513") (pin "SW1") (pinfunction "SW1_SW1") (pintype "bidirectional"))
      (node (ref "K613") (pin "SW1") (pinfunction "SW1_SW1") (pintype "bidirectional"))
    )
    (net (code "104") (name "Net-(K114-PadSW1)") (class "Default")
      (node (ref "K114") (pin "SW1") (pinfunction "SW1_SW1") (pintype "bidirectional"))
      (node (ref "K214") (pin "SW1") (pinfunction "SW1_SW1") (pintype "bidirectional"))
      (node (ref "K314") (pin "SW1") (pinfunction "SW1_SW1") (pintype "bidirectional"))
      (node (ref "K414") (pin "SW1") (pinfunction "SW1_SW1") (pintype "bidirectional"))
      (node (ref "K514") (pin "SW1") (pinfunction "SW1_SW1") (pintype "bidirectional"))
      (node (ref "K614") (pin "SW1") (pinfunction "SW1_SW1") (pintype "bidirectional"))
    )
    (net (code "105") (name "Net-(K115-PadSW1)") (class "Default")
      (node (ref "K115") (pin "SW1") (pinfunction "SW1_SW1") (pintype "bidirectional"))
      (node (ref "K215") (pin "SW1") (pinfunction "SW1_SW1") (pintype "bidirectional"))
      (node (ref "K315") (pin "SW1") (pinfunction "SW1_SW1") (pintype "bidirectional"))
      (node (ref "K415") (pin "SW1") (pinfunction "SW1_SW1") (pintype "bidirectional"))
      (node (ref "K515") (pin "SW1") (pinfunction "SW1_SW1") (pintype "bidirectional"))
      (node (ref "K615") (pin "SW1") (pinfunction "SW1_SW1") (pintype "bidirectional"))
    )
    (net (code "106") (name "Net-(Q1-D)") (class "Default")
      (node (ref "Q1") (pin "2") (pinfunction "D_2") (pintype "passive"))
      (node (ref "Q2") (pin "2") (pinfunction "D_2") (pintype "passive"))
      (node (ref "Q3") (pin "2") (pinfunction "D_2") (pintype "passive"))
      (node (ref "Q4") (pin "2") (pinfunction "D_2") (pintype "passive"))
      (node (ref "Q5") (pin "2") (pinfunction "D_2") (pintype "passive"))
      (node (ref "Q6") (pin "2") (pinfunction "D_2") (pintype "passive"))
    )
    (net (code "107") (name "Net-(Q1-G)") (class "Default")
      (node (ref "D11") (pin "C") (pinfunction "C_C") (pintype "passive"))
      (node (ref "D110") (pin "C") (pinfunction "C_C") (pintype "passive"))
      (node (ref "D111") (pin "C") (pinfunction "C_C") (pintype "passive"))
      (node (ref "D112") (pin "C") (pinfunction "C_C") (pintype "passive"))
      (node (ref "D113") (pin "C") (pinfunction "C_C") (pintype "passive"))
      (node (ref "D114") (pin "C") (pinfunction "C_C") (pintype "passive"))
      (node (ref "D115") (pin "C") (pinfunction "C_C") (pintype "passive"))
      (node (ref "D12") (pin "C") (pinfunction "C_C") (pintype "passive"))
      (node (ref "D13") (pin "C") (pinfunction "C_C") (pintype "passive"))
      (node (ref "D14") (pin "C") (pinfunction "C_C") (pintype "passive"))
      (node (ref "D15") (pin "C") (pinfunction "C_C") (pintype "passive"))
      (node (ref "D16") (pin "C") (pinfunction "C_C") (pintype "passive"))
      (node (ref "D17") (pin "C") (pinfunction "C_C") (pintype "passive"))
      (node (ref "D18") (pin "C") (pinfunction "C_C") (pintype "passive"))
      (node (ref "D19") (pin "C") (pinfunction "C_C") (pintype "passive"))
      (node (ref "Q1") (pin "1") (pinfunction "G_1") (pintype "passive"))
    )
    (net (code "108") (name "Net-(Q1-S)") (class "Default")
      (node (ref "Q1") (pin "3") (pinfunction "S_3") (pintype "passive"))
      (node (ref "R8") (pin "1") (pinfunction "1_1") (pintype "passive"))
    )
    (net (code "109") (name "Net-(Q2-G)") (class "Default")
      (node (ref "D21") (pin "C") (pinfunction "C_C") (pintype "passive"))
      (node (ref "D210") (pin "C") (pinfunction "C_C") (pintype "passive"))
      (node (ref "D211") (pin "C") (pinfunction "C_C") (pintype "passive"))
      (node (ref "D212") (pin "C") (pinfunction "C_C") (pintype "passive"))
      (node (ref "D213") (pin "C") (pinfunction "C_C") (pintype "passive"))
      (node (ref "D214") (pin "C") (pinfunction "C_C") (pintype "passive"))
      (node (ref "D215") (pin "C") (pinfunction "C_C") (pintype "passive"))
      (node (ref "D22") (pin "C") (pinfunction "C_C") (pintype "passive"))
      (node (ref "D23") (pin "C") (pinfunction "C_C") (pintype "passive"))
      (node (ref "D24") (pin "C") (pinfunction "C_C") (pintype "passive"))
      (node (ref "D25") (pin "C") (pinfunction "C_C") (pintype "passive"))
      (node (ref "D26") (pin "C") (pinfunction "C_C") (pintype "passive"))
      (node (ref "D27") (pin "C") (pinfunction "C_C") (pintype "passive"))
      (node (ref "D28") (pin "C") (pinfunction "C_C") (pintype "passive"))
      (node (ref "D29") (pin "C") (pinfunction "C_C") (pintype "passive"))
      (node (ref "Q2") (pin "1") (pinfunction "G_1") (pintype "passive"))
    )
    (net (code "110") (name "Net-(Q2-S)") (class "Default")
      (node (ref "Q2") (pin "3") (pinfunction "S_3") (pintype "passive"))
      (node (ref "R2") (pin "1") (pinfunction "1_1") (pintype "passive"))
    )
    (net (code "111") (name "Net-(Q3-G)") (class "Default")
      (node (ref "311") (pin "C") (pinfunction "C_C") (pintype "passive"))
      (node (ref "D31") (pin "C") (pinfunction "C_C") (pintype "passive"))
      (node (ref "D310") (pin "C") (pinfunction "C_C") (pintype "passive"))
      (node (ref "D312") (pin "C") (pinfunction "C_C") (pintype "passive"))
      (node (ref "D313") (pin "C") (pinfunction "C_C") (pintype "passive"))
      (node (ref "D314") (pin "C") (pinfunction "C_C") (pintype "passive"))
      (node (ref "D315") (pin "C") (pinfunction "C_C") (pintype "passive"))
      (node (ref "D32") (pin "C") (pinfunction "C_C") (pintype "passive"))
      (node (ref "D33") (pin "C") (pinfunction "C_C") (pintype "passive"))
      (node (ref "D34") (pin "C") (pinfunction "C_C") (pintype "passive"))
      (node (ref "D35") (pin "C") (pinfunction "C_C") (pintype "passive"))
      (node (ref "D36") (pin "C") (pinfunction "C_C") (pintype "passive"))
      (node (ref "D37") (pin "C") (pinfunction "C_C") (pintype "passive"))
      (node (ref "D38") (pin "C") (pinfunction "C_C") (pintype "passive"))
      (node (ref "D39") (pin "C") (pinfunction "C_C") (pintype "passive"))
      (node (ref "Q3") (pin "1") (pinfunction "G_1") (pintype "passive"))
    )
    (net (code "112") (name "Net-(Q3-S)") (class "Default")
      (node (ref "Q3") (pin "3") (pinfunction "S_3") (pintype "passive"))
      (node (ref "R1") (pin "1") (pinfunction "1_1") (pintype "passive"))
    )
    (net (code "113") (name "Net-(Q4-G)") (class "Default")
      (node (ref "411") (pin "C") (pinfunction "C_C") (pintype "passive"))
      (node (ref "D41") (pin "C") (pinfunction "C_C") (pintype "passive"))
      (node (ref "D410") (pin "C") (pinfunction "C_C") (pintype "passive"))
      (node (ref "D412") (pin "C") (pinfunction "C_C") (pintype "passive"))
      (node (ref "D413") (pin "C") (pinfunction "C_C") (pintype "passive"))
      (node (ref "D414") (pin "C") (pinfunction "C_C") (pintype "passive"))
      (node (ref "D415") (pin "C") (pinfunction "C_C") (pintype "passive"))
      (node (ref "D42") (pin "C") (pinfunction "C_C") (pintype "passive"))
      (node (ref "D43") (pin "C") (pinfunction "C_C") (pintype "passive"))
      (node (ref "D44") (pin "C") (pinfunction "C_C") (pintype "passive"))
      (node (ref "D45") (pin "C") (pinfunction "C_C") (pintype "passive"))
      (node (ref "D46") (pin "C") (pinfunction "C_C") (pintype "passive"))
      (node (ref "D47") (pin "C") (pinfunction "C_C") (pintype "passive"))
      (node (ref "D48") (pin "C") (pinfunction "C_C") (pintype "passive"))
      (node (ref "D49") (pin "C") (pinfunction "C_C") (pintype "passive"))
      (node (ref "Q4") (pin "1") (pinfunction "G_1") (pintype "passive"))
    )
    (net (code "114") (name "Net-(Q4-S)") (class "Default")
      (node (ref "Q4") (pin "3") (pinfunction "S_3") (pintype "passive"))
      (node (ref "R6") (pin "1") (pinfunction "1_1") (pintype "passive"))
    )
    (net (code "115") (name "Net-(Q5-G)") (class "Default")
      (node (ref "D51") (pin "C") (pinfunction "C_C") (pintype "passive"))
      (node (ref "D510") (pin "C") (pinfunction "C_C") (pintype "passive"))
      (node (ref "D511") (pin "C") (pinfunction "C_C") (pintype "passive"))
      (node (ref "D513") (pin "C") (pinfunction "C_C") (pintype "passive"))
      (node (ref "D514") (pin "C") (pinfunction "C_C") (pintype "passive"))
      (node (ref "D515") (pin "C") (pinfunction "C_C") (pintype "passive"))
      (node (ref "D52") (pin "C") (pinfunction "C_C") (pintype "passive"))
      (node (ref "D53") (pin "C") (pinfunction "C_C") (pintype "passive"))
      (node (ref "D54") (pin "C") (pinfunction "C_C") (pintype "passive"))
      (node (ref "D55") (pin "C") (pinfunction "C_C") (pintype "passive"))
      (node (ref "D56") (pin "C") (pinfunction "C_C") (pintype "passive"))
      (node (ref "D57") (pin "C") (pinfunction "C_C") (pintype "passive"))
      (node (ref "D58") (pin "C") (pinfunction "C_C") (pintype "passive"))
      (node (ref "D59") (pin "C") (pinfunction "C_C") (pintype "passive"))
      (node (ref "Q5") (pin "1") (pinfunction "G_1") (pintype "passive"))
    )
    (net (code "116") (name "Net-(Q5-S)") (class "Default")
      (node (ref "Q5") (pin "3") (pinfunction "S_3") (pintype "passive"))
      (node (ref "R7") (pin "1") (pinfunction "1_1") (pintype "passive"))
    )
    (net (code "117") (name "Net-(Q6-G)") (class "Default")
      (node (ref "D61") (pin "C") (pinfunction "C_C") (pintype "passive"))
      (node (ref "D610") (pin "C") (pinfunction "C_C") (pintype "passive"))
      (node (ref "D611") (pin "C") (pinfunction "C_C") (pintype "passive"))
      (node (ref "D612") (pin "C") (pinfunction "C_C") (pintype "passive"))
      (node (ref "D613") (pin "C") (pinfunction "C_C") (pintype "passive"))
      (node (ref "D614") (pin "C") (pinfunction "C_C") (pintype "passive"))
      (node (ref "D615") (pin "C") (pinfunction "C_C") (pintype "passive"))
      (node (ref "D62") (pin "C") (pinfunction "C_C") (pintype "passive"))
      (node (ref "D63") (pin "C") (pinfunction "C_C") (pintype "passive"))
      (node (ref "D66") (pin "C") (pinfunction "C_C") (pintype "passive"))
      (node (ref "Q6") (pin "1") (pinfunction "G_1") (pintype "passive"))
    )
    (net (code "118") (name "Net-(Q6-S)") (class "Default")
      (node (ref "Q6") (pin "3") (pinfunction "S_3") (pintype "passive"))
      (node (ref "R3") (pin "1") (pinfunction "1_1") (pintype "passive"))
    )
    (net (code "119") (name "Net-(Q7-D)") (class "Default")
      (node (ref "K11") (pin "LED-") (pinfunction "LED-_LED-") (pintype "bidirectional"))
      (node (ref "K110") (pin "LED-") (pinfunction "LED-_LED-") (pintype "bidirectional"))
      (node (ref "K111") (pin "LED-") (pinfunction "LED-_LED-") (pintype "bidirectional"))
      (node (ref "K112") (pin "LED-") (pinfunction "LED-_LED-") (pintype "bidirectional"))
      (node (ref "K113") (pin "LED-") (pinfunction "LED-_LED-") (pintype "bidirectional"))
      (node (ref "K114") (pin "LED-") (pinfunction "LED-_LED-") (pintype "bidirectional"))
      (node (ref "K115") (pin "LED-") (pinfunction "LED-_LED-") (pintype "bidirectional"))
      (node (ref "K12") (pin "LED-") (pinfunction "LED-_LED-") (pintype "bidirectional"))
      (node (ref "K13") (pin "LED-") (pinfunction "LED-_LED-") (pintype "bidirectional"))
      (node (ref "K14") (pin "LED-") (pinfunction "LED-_LED-") (pintype "bidirectional"))
      (node (ref "K15") (pin "LED-") (pinfunction "LED-_LED-") (pintype "bidirectional"))
      (node (ref "K16") (pin "LED-") (pinfunction "LED-_LED-") (pintype "bidirectional"))
      (node (ref "K17") (pin "LED-") (pinfunction "LED-_LED-") (pintype "bidirectional"))
      (node (ref "K18") (pin "LED-") (pinfunction "LED-_LED-") (pintype "bidirectional"))
      (node (ref "K19") (pin "LED-") (pinfunction "LED-_LED-") (pintype "bidirectional"))
      (node (ref "K21") (pin "LED-") (pinfunction "LED-_LED-") (pintype "bidirectional"))
      (node (ref "K210") (pin "LED-") (pinfunction "LED-_LED-") (pintype "bidirectional"))
      (node (ref "K211") (pin "LED-") (pinfunction "LED-_LED-") (pintype "bidirectional"))
      (node (ref "K212") (pin "LED-") (pinfunction "LED-_LED-") (pintype "bidirectional"))
      (node (ref "K213") (pin "LED-") (pinfunction "LED-_LED-") (pintype "bidirectional"))
      (node (ref "K214") (pin "LED-") (pinfunction "LED-_LED-") (pintype "bidirectional"))
      (node (ref "K215") (pin "LED-") (pinfunction "LED-_LED-") (pintype "bidirectional"))
      (node (ref "K22") (pin "LED-") (pinfunction "LED-_LED-") (pintype "bidirectional"))
      (node (ref "K23") (pin "LED-") (pinfunction "LED-_LED-") (pintype "bidirectional"))
      (node (ref "K24") (pin "LED-") (pinfunction "LED-_LED-") (pintype "bidirectional"))
      (node (ref "K25") (pin "LED-") (pinfunction "LED-_LED-") (pintype "bidirectional"))
      (node (ref "K26") (pin "LED-") (pinfunction "LED-_LED-") (pintype "bidirectional"))
      (node (ref "K27") (pin "LED-") (pinfunction "LED-_LED-") (pintype "bidirectional"))
      (node (ref "K28") (pin "LED-") (pinfunction "LED-_LED-") (pintype "bidirectional"))
      (node (ref "K29") (pin "LED-") (pinfunction "LED-_LED-") (pintype "bidirectional"))
      (node (ref "K31") (pin "LED-") (pinfunction "LED-_LED-") (pintype "bidirectional"))
      (node (ref "K310") (pin "LED-") (pinfunction "LED-_LED-") (pintype "bidirectional"))
      (node (ref "K311") (pin "LED-") (pinfunction "LED-_LED-") (pintype "bidirectional"))
      (node (ref "K312") (pin "LED-") (pinfunction "LED-_LED-") (pintype "bidirectional"))
      (node (ref "K313") (pin "LED-") (pinfunction "LED-_LED-") (pintype "bidirectional"))
      (node (ref "K314") (pin "LED-") (pinfunction "LED-_LED-") (pintype "bidirectional"))
      (node (ref "K315") (pin "LED-") (pinfunction "LED-_LED-") (pintype "bidirectional"))
      (node (ref "K32") (pin "LED-") (pinfunction "LED-_LED-") (pintype "bidirectional"))
      (node (ref "K33") (pin "LED-") (pinfunction "LED-_LED-") (pintype "bidirectional"))
      (node (ref "K34") (pin "LED-") (pinfunction "LED-_LED-") (pintype "bidirectional"))
      (node (ref "K35") (pin "LED-") (pinfunction "LED-_LED-") (pintype "bidirectional"))
      (node (ref "K36") (pin "LED-") (pinfunction "LED-_LED-") (pintype "bidirectional"))
      (node (ref "K37") (pin "LED-") (pinfunction "LED-_LED-") (pintype "bidirectional"))
      (node (ref "K38") (pin "LED-") (pinfunction "LED-_LED-") (pintype "bidirectional"))
      (node (ref "K39") (pin "LED-") (pinfunction "LED-_LED-") (pintype "bidirectional"))
      (node (ref "K41") (pin "LED-") (pinfunction "LED-_LED-") (pintype "bidirectional"))
      (node (ref "K410") (pin "LED-") (pinfunction "LED-_LED-") (pintype "bidirectional"))
      (node (ref "K411") (pin "LED-") (pinfunction "LED-_LED-") (pintype "bidirectional"))
      (node (ref "K412") (pin "LED-") (pinfunction "LED-_LED-") (pintype "bidirectional"))
      (node (ref "K413") (pin "LED-") (pinfunction "LED-_LED-") (pintype "bidirectional"))
      (node (ref "K414") (pin "LED-") (pinfunction "LED-_LED-") (pintype "bidirectional"))
      (node (ref "K415") (pin "LED-") (pinfunction "LED-_LED-") (pintype "bidirectional"))
      (node (ref "K43") (pin "LED-") (pinfunction "LED-_LED-") (pintype "bidirectional"))
      (node (ref "K44") (pin "LED-") (pinfunction "LED-_LED-") (pintype "bidirectional"))
      (node (ref "K45") (pin "LED-") (pinfunction "LED-_LED-") (pintype "bidirectional"))
      (node (ref "K46") (pin "LED-") (pinfunction "LED-_LED-") (pintype "bidirectional"))
      (node (ref "K47") (pin "LED-") (pinfunction "LED-_LED-") (pintype "bidirectional"))
      (node (ref "K48") (pin "LED-") (pinfunction "LED-_LED-") (pintype "bidirectional"))
      (node (ref "K49") (pin "LED-") (pinfunction "LED-_LED-") (pintype "bidirectional"))
      (node (ref "K51") (pin "LED-") (pinfunction "LED-_LED-") (pintype "bidirectional"))
      (node (ref "K510") (pin "LED-") (pinfunction "LED-_LED-") (pintype "bidirectional"))
      (node (ref "K511") (pin "LED-") (pinfunction "LED-_LED-") (pintype "bidirectional"))
      (node (ref "K513") (pin "LED-") (pinfunction "LED-_LED-") (pintype "bidirectional"))
      (node (ref "K514") (pin "LED-") (pinfunction "LED-_LED-") (pintype "bidirectional"))
      (node (ref "K515") (pin "LED-") (pinfunction "LED-_LED-") (pintype "bidirectional"))
      (node (ref "K52") (pin "LED-") (pinfunction "LED-_LED-") (pintype "bidirectional"))
      (node (ref "K53") (pin "LED-") (pinfunction "LED-_LED-") (pintype "bidirectional"))
      (node (ref "K54") (pin "LED-") (pinfunction "LED-_LED-") (pintype "bidirectional"))
      (node (ref "K55") (pin "LED-") (pinfunction "LED-_LED-") (pintype "bidirectional"))
      (node (ref "K56") (pin "LED-") (pinfunction "LED-_LED-") (pintype "bidirectional"))
      (node (ref "K57") (pin "LED-") (pinfunction "LED-_LED-") (pintype "bidirectional"))
      (node (ref "K58") (pin "LED-") (pinfunction "LED-_LED-") (pintype "bidirectional"))
      (node (ref "K59") (pin "LED-") (pinfunction "LED-_LED-") (pintype "bidirectional"))
      (node (ref "K61") (pin "LED-") (pinfunction "LED-_LED-") (pintype "bidirectional"))
      (node (ref "K610") (pin "LED-") (pinfunction "LED-_LED-") (pintype "bidirectional"))
      (node (ref "K611") (pin "LED-") (pinfunction "LED-_LED-") (pintype "bidirectional"))
      (node (ref "K612") (pin "LED-") (pinfunction "LED-_LED-") (pintype "bidirectional"))
      (node (ref "K613") (pin "LED-") (pinfunction "LED-_LED-") (pintype "bidirectional"))
      (node (ref "K614") (pin "LED-") (pinfunction "LED-_LED-") (pintype "bidirectional"))
      (node (ref "K615") (pin "LED-") (pinfunction "LED-_LED-") (pintype "bidirectional"))
      (node (ref "K62") (pin "LED-") (pinfunction "LED-_LED-") (pintype "bidirectional"))
      (node (ref "K63") (pin "LED-") (pinfunction "LED-_LED-") (pintype "bidirectional"))
      (node (ref "K66") (pin "LED-") (pinfunction "LED-_LED-") (pintype "bidirectional"))
      (node (ref "Q7") (pin "2") (pinfunction "D_2") (pintype "passive"))
    )
    (net (code "120") (name "Net-(Q7-G)") (class "Default")
      (node (ref "Q7") (pin "1") (pinfunction "G_1") (pintype "passive"))
      (node (ref "_1") (pin "B7") (pinfunction "_B7_B7") (pintype "bidirectional"))
    )
    (net (code "121") (name "unconnected-(JP1-Pad1)") (class "Default")
      (node (ref "JP1") (pin "1") (pinfunction "1_1") (pintype "passive"))
    )
    (net (code "122") (name "unconnected-(JP1-Pad2)") (class "Default")
      (node (ref "JP1") (pin "2") (pinfunction "2_2") (pintype "passive"))
    )
    (net (code "123") (name "unconnected-(JP1-Pad3)") (class "Default")
      (node (ref "JP1") (pin "3") (pinfunction "3_3") (pintype "passive"))
    )
    (net (code "124") (name "unconnected-(JP1-Pad4)") (class "Default")
      (node (ref "JP1") (pin "4") (pinfunction "4_4") (pintype "passive"))
    )
    (net (code "125") (name "unconnected-(K25-PadSW1)") (class "Default")
      (node (ref "K25") (pin "SW1") (pinfunction "SW1_SW1") (pintype "bidirectional"))
    )
    (net (code "126") (name "unconnected-(K42-PadLED-)") (class "Default")
      (node (ref "K42") (pin "LED-") (pinfunction "LED-_LED-") (pintype "bidirectional"))
    )
    (net (code "127") (name "unconnected-(Q7-S-Pad3)") (class "Default")
      (node (ref "Q7") (pin "3") (pinfunction "S_3") (pintype "passive"))
    )
    (net (code "128") (name "unconnected-(R4-Pad1)") (class "Default")
      (node (ref "R4") (pin "1") (pinfunction "1_1") (pintype "passive"))
    )
    (net (code "129") (name "unconnected-(R4-Pad2)") (class "Default")
      (node (ref "R4") (pin "2") (pinfunction "2_2") (pintype "passive"))
    )
    (net (code "130") (name "unconnected-(R5-Pad1)") (class "Default")
      (node (ref "R5") (pin "1") (pinfunction "1_1") (pintype "passive"))
    )
    (net (code "131") (name "unconnected-(R5-Pad2)") (class "Default")
      (node (ref "R5") (pin "2") (pinfunction "2_2") (pintype "passive"))
    )
    (net (code "132") (name "unconnected-(_1-5V-Pad+5V)") (class "Default")
      (node (ref "_1") (pin "+5V") (pinfunction "5V_+5V") (pintype "bidirectional"))
    )
    (net (code "133") (name "unconnected-(_1-_5V2-Pad5V2)") (class "Default")
      (node (ref "_1") (pin "5V2") (pinfunction "_5V2_5V2") (pintype "bidirectional"))
    )
    (net (code "134") (name "unconnected-(_1-_B0-PadB0)") (class "Default")
      (node (ref "_1") (pin "B0") (pinfunction "_B0_B0") (pintype "bidirectional"))
    )
    (net (code "135") (name "unconnected-(_1-_B1-PadB1)") (class "Default")
      (node (ref "_1") (pin "B1") (pinfunction "_B1_B1") (pintype "bidirectional"))
    )
    (net (code "136") (name "unconnected-(_1-_B2-PadB2)") (class "Default")
      (node (ref "_1") (pin "B2") (pinfunction "_B2_B2") (pintype "bidirectional"))
    )
    (net (code "137") (name "unconnected-(_1-_B3-PadB3)") (class "Default")
      (node (ref "_1") (pin "B3") (pinfunction "_B3_B3") (pintype "bidirectional"))
    )
    (net (code "138") (name "unconnected-(_1-_B4-PadB4)") (class "Default")
      (node (ref "_1") (pin "B4") (pinfunction "_B4_B4") (pintype "bidirectional"))
    )
    (net (code "139") (name "unconnected-(_1-_B5-PadB5)") (class "Default")
      (node (ref "_1") (pin "B5") (pinfunction "_B5_B5") (pintype "bidirectional"))
    )
    (net (code "140") (name "unconnected-(_1-_B6-PadB6)") (class "Default")
      (node (ref "_1") (pin "B6") (pinfunction "_B6_B6") (pintype "bidirectional"))
    )
    (net (code "141") (name "unconnected-(_1-_C6-PadC6)") (class "Default")
      (node (ref "_1") (pin "C6") (pinfunction "_C6_C6") (pintype "bidirectional"))
    )
    (net (code "142") (name "unconnected-(_1-_C7-PadC7)") (class "Default")
      (node (ref "_1") (pin "C7") (pinfunction "_C7_C7") (pintype "bidirectional"))
    )
    (net (code "143") (name "unconnected-(_1-_D0-PadD0)") (class "Default")
      (node (ref "_1") (pin "D0") (pinfunction "_D0_D0") (pintype "bidirectional"))
    )
    (net (code "144") (name "unconnected-(_1-_D1-PadD1)") (class "Default")
      (node (ref "_1") (pin "D1") (pinfunction "_D1_D1") (pintype "bidirectional"))
    )
    (net (code "145") (name "unconnected-(_1-_D2-PadD2)") (class "Default")
      (node (ref "_1") (pin "D2") (pinfunction "_D2_D2") (pintype "bidirectional"))
    )
    (net (code "146") (name "unconnected-(_1-_D3-PadD3)") (class "Default")
      (node (ref "_1") (pin "D3") (pinfunction "_D3_D3") (pintype "bidirectional"))
    )
    (net (code "147") (name "unconnected-(_1-_D4-PadD4)") (class "Default")
      (node (ref "_1") (pin "D4") (pinfunction "_D4_D4") (pintype "bidirectional"))
    )
    (net (code "148") (name "unconnected-(_1-_D5-PadD5)") (class "Default")
      (node (ref "_1") (pin "D5") (pinfunction "_D5_D5") (pintype "bidirectional"))
    )
    (net (code "149") (name "unconnected-(_1-_D6-PadD6)") (class "Default")
      (node (ref "_1") (pin "D6") (pinfunction "_D6_D6") (pintype "bidirectional"))
    )
    (net (code "150") (name "unconnected-(_1-_D7-PadD7)") (class "Default")
      (node (ref "_1") (pin "D7") (pinfunction "_D7_D7") (pintype "bidirectional"))
    )
    (net (code "151") (name "unconnected-(_1-_E6-PadE6)") (class "Default")
      (node (ref "_1") (pin "E6") (pinfunction "_E6_E6") (pintype "bidirectional"))
    )
    (net (code "152") (name "unconnected-(_1-_F0-PadF0)") (class "Default")
      (node (ref "_1") (pin "F0") (pinfunction "_F0_F0") (pintype "bidirectional"))
    )
    (net (code "153") (name "unconnected-(_1-_F1-PadF1)") (class "Default")
      (node (ref "_1") (pin "F1") (pinfunction "_F1_F1") (pintype "bidirectional"))
    )
    (net (code "154") (name "unconnected-(_1-_F4-PadF4)") (class "Default")
      (node (ref "_1") (pin "F4") (pinfunction "_F4_F4") (pintype "bidirectional"))
    )
    (net (code "155") (name "unconnected-(_1-_F5-PadF5)") (class "Default")
      (node (ref "_1") (pin "F5") (pinfunction "_F5_F5") (pintype "bidirectional"))
    )
    (net (code "156") (name "unconnected-(_1-_F6-PadF6)") (class "Default")
      (node (ref "_1") (pin "F6") (pinfunction "_F6_F6") (pintype "bidirectional"))
    )
    (net (code "157") (name "unconnected-(_1-_F7-PadF7)") (class "Default")
      (node (ref "_1") (pin "F7") (pinfunction "_F7_F7") (pintype "bidirectional"))
    )
    (net (code "158") (name "unconnected-(_1-_GND-PadGND)") (class "Default")
      (node (ref "_1") (pin "GND") (pinfunction "_GND_GND") (pintype "bidirectional"))
    )
    (net (code "159") (name "unconnected-(_1-_GND1-PadGRND1)") (class "Default")
      (node (ref "_1") (pin "GRND1") (pinfunction "_GND1_GRND1") (pintype "bidirectional"))
    )
    (net (code "160") (name "unconnected-(_1-_REF-PadREF)") (class "Default")
      (node (ref "_1") (pin "REF") (pinfunction "_REF_REF") (pintype "bidirectional"))
    )
    (net (code "161") (name "unconnected-(_1-_RST-PadRST)") (class "Default")
      (node (ref "_1") (pin "RST") (pinfunction "_RST_RST") (pintype "bidirectional"))
    )
  )
)
